# Breadboard.net
KiCad netlist of a schematic drawn in EAGLE
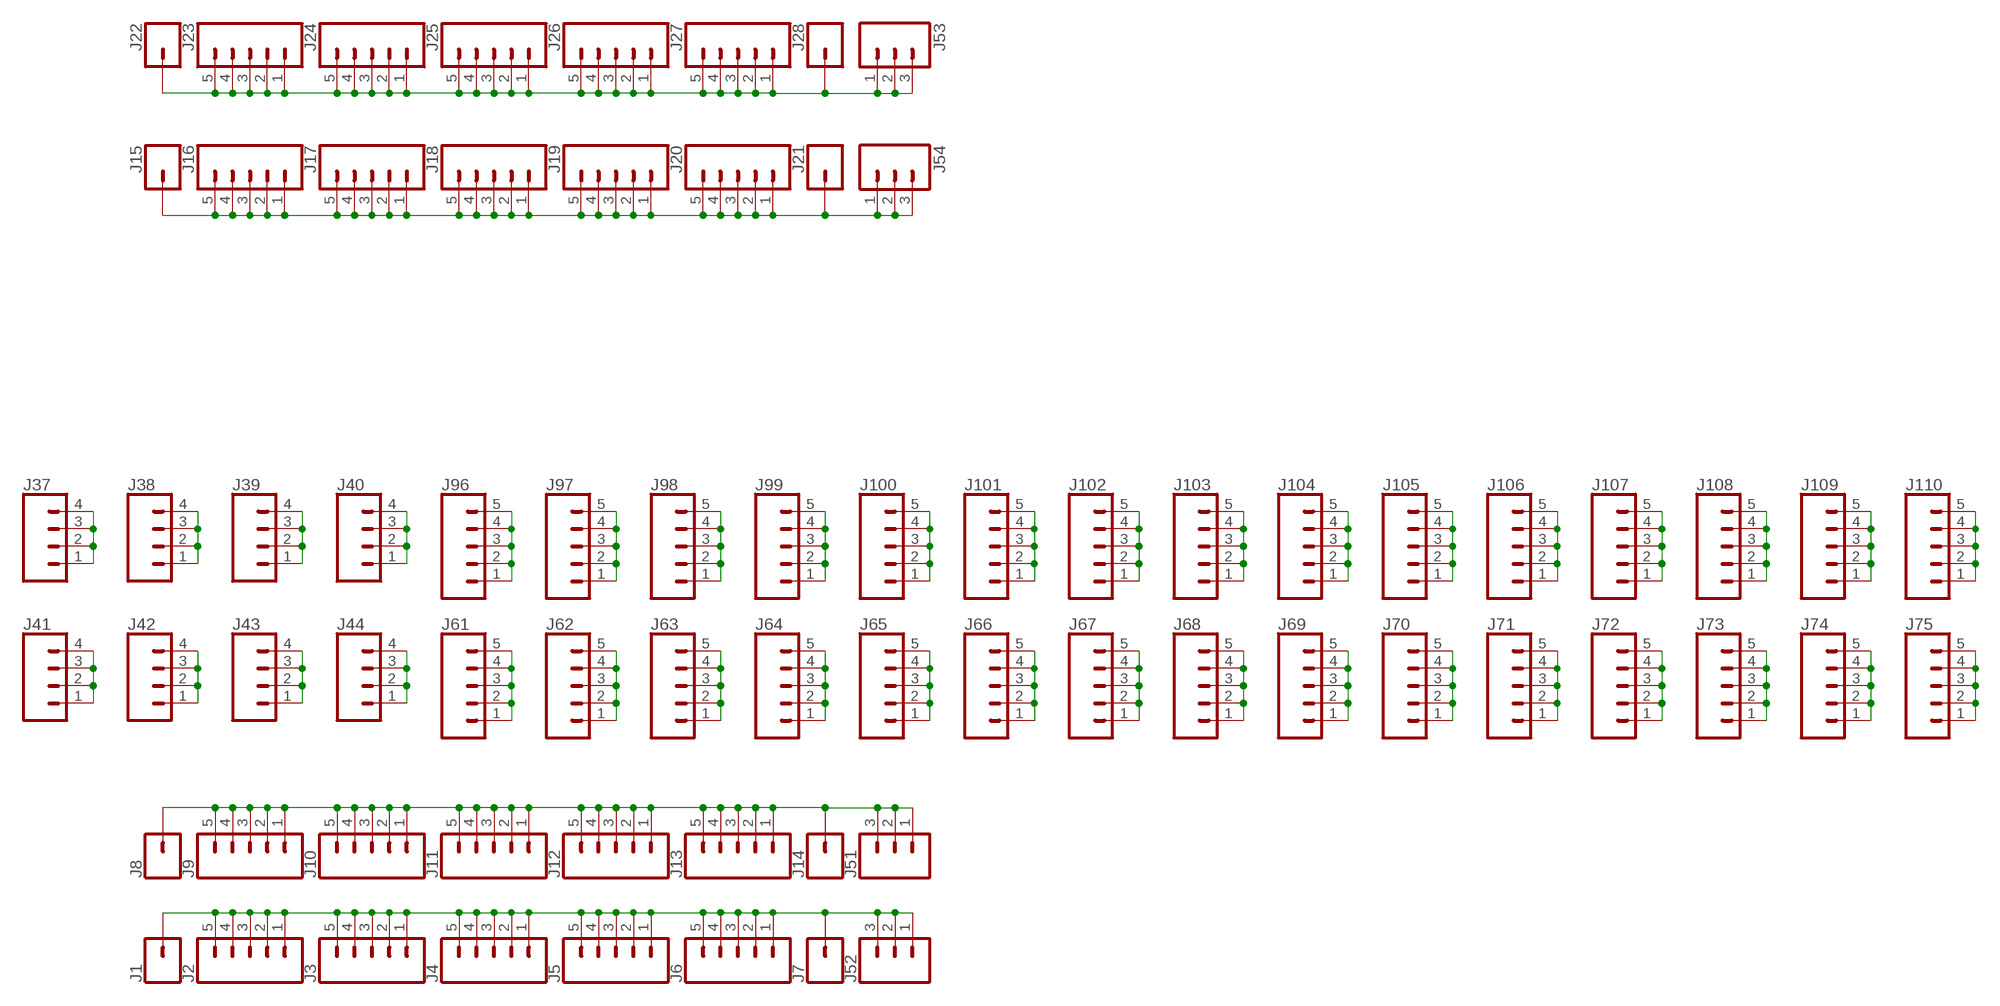
[diagram p0: schematic, sheet 1, part 1 of 2]
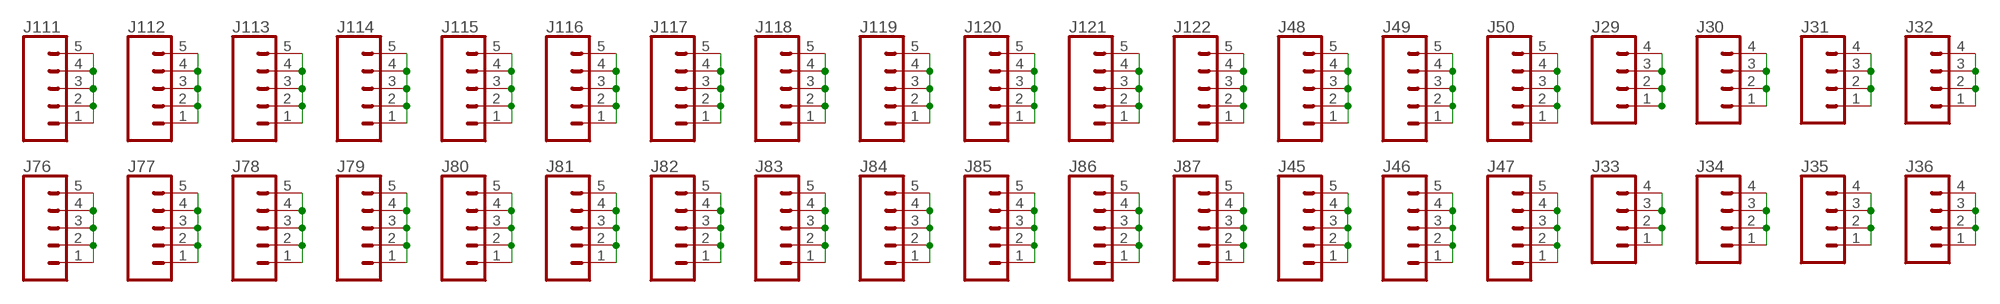
[diagram p1: schematic, sheet 1, part 2 of 2]
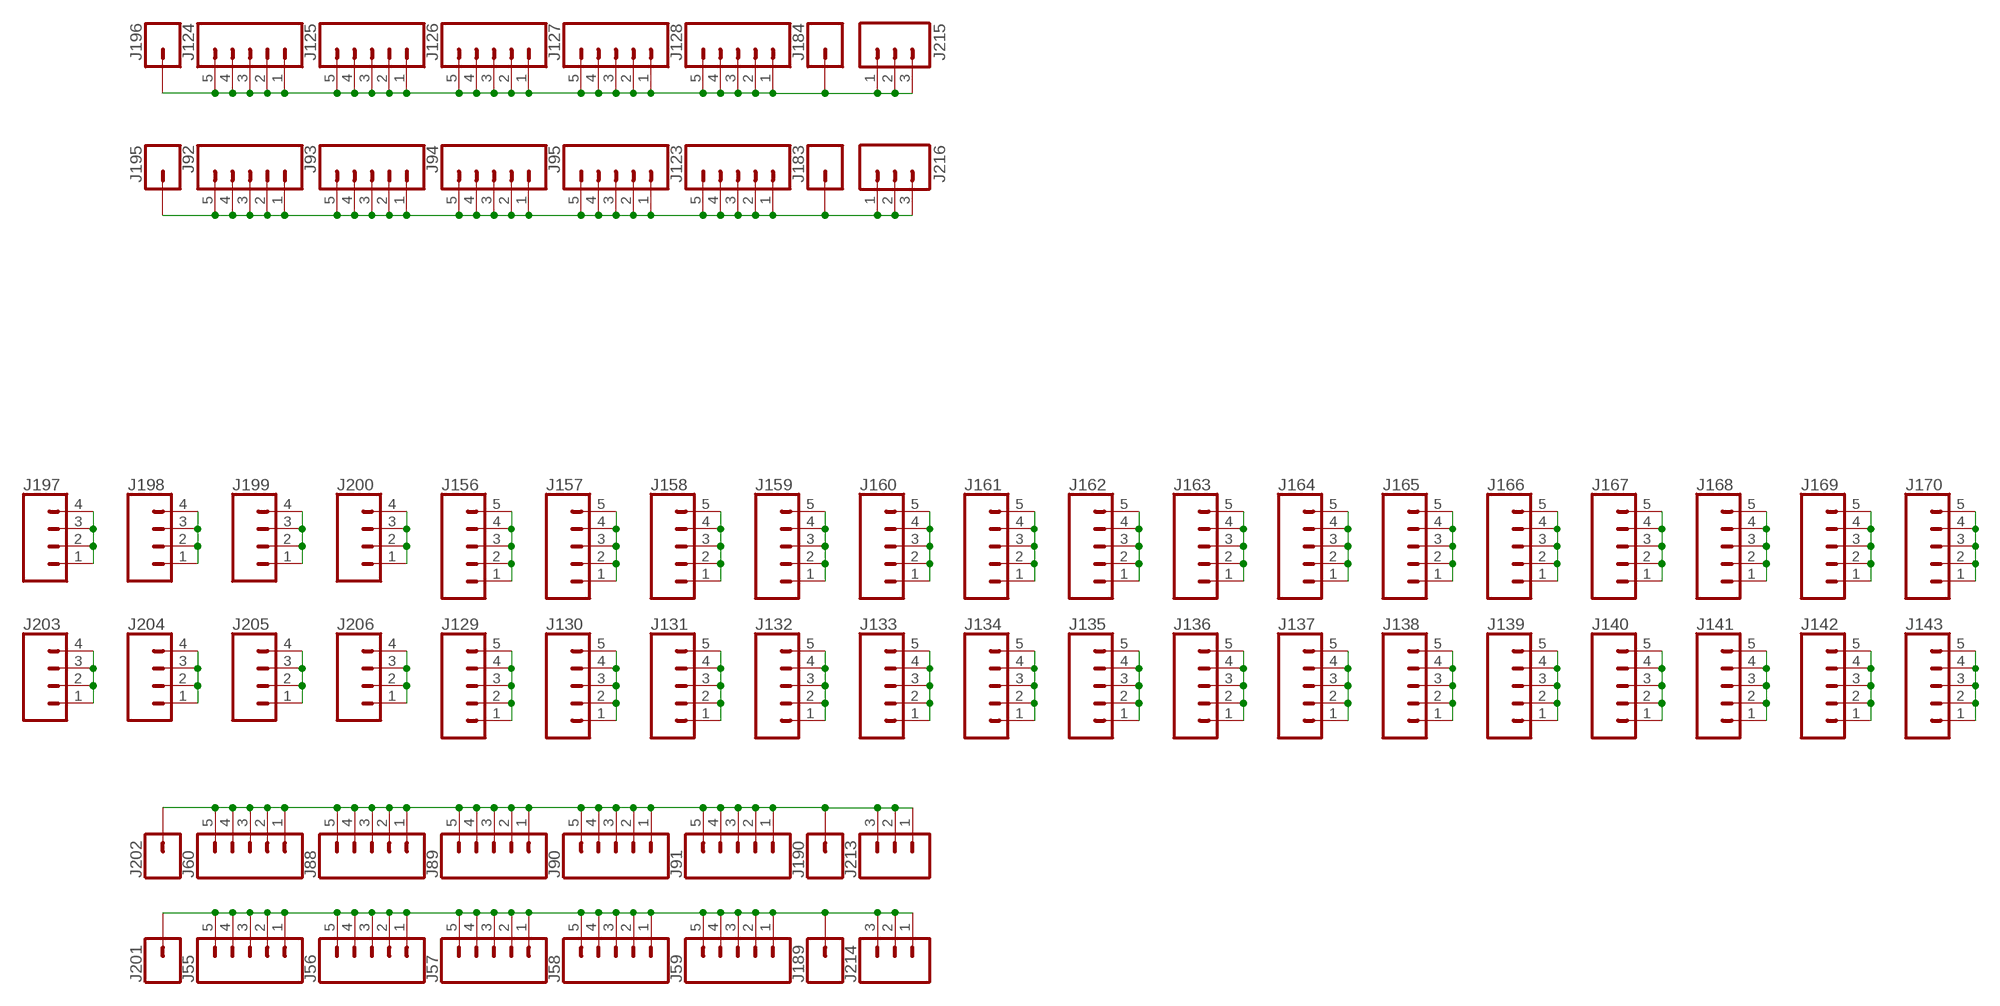
[diagram p2: schematic, sheet 2, part 1 of 2]
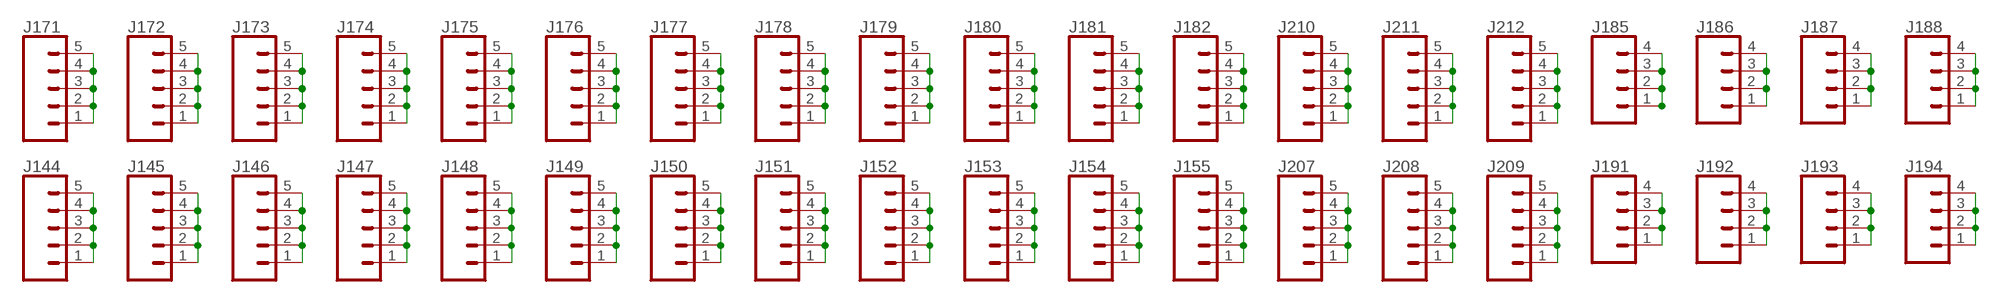
[diagram p3: schematic, sheet 2, part 2 of 2]

(export (version "E")
  (design (tool "Eeschema 10.0.6"))
  (components
    (comp (ref "J1")
      (value "CONN_01")
      (footprint "eagle-import:1X01")
      (libsource (lib "eagle-import") (part "CONN_01"))
    )
    (comp (ref "J2")
      (value "CONN_05")
      (footprint "eagle-import:1X05")
      (libsource (lib "eagle-import") (part "CONN_05"))
    )
    (comp (ref "J3")
      (value "CONN_05")
      (footprint "eagle-import:1X05")
      (libsource (lib "eagle-import") (part "CONN_05"))
    )
    (comp (ref "J4")
      (value "CONN_05")
      (footprint "eagle-import:1X05")
      (libsource (lib "eagle-import") (part "CONN_05"))
    )
    (comp (ref "J5")
      (value "CONN_05")
      (footprint "eagle-import:1X05")
      (libsource (lib "eagle-import") (part "CONN_05"))
    )
    (comp (ref "J6")
      (value "CONN_05")
      (footprint "eagle-import:1X05")
      (libsource (lib "eagle-import") (part "CONN_05"))
    )
    (comp (ref "J7")
      (value "CONN_01")
      (footprint "eagle-import:1X01")
      (libsource (lib "eagle-import") (part "CONN_01"))
    )
    (comp (ref "J8")
      (value "CONN_01")
      (footprint "eagle-import:1X01")
      (libsource (lib "eagle-import") (part "CONN_01"))
    )
    (comp (ref "J9")
      (value "CONN_05")
      (footprint "eagle-import:1X05")
      (libsource (lib "eagle-import") (part "CONN_05"))
    )
    (comp (ref "J10")
      (value "CONN_05")
      (footprint "eagle-import:1X05")
      (libsource (lib "eagle-import") (part "CONN_05"))
    )
    (comp (ref "J11")
      (value "CONN_05")
      (footprint "eagle-import:1X05")
      (libsource (lib "eagle-import") (part "CONN_05"))
    )
    (comp (ref "J12")
      (value "CONN_05")
      (footprint "eagle-import:1X05")
      (libsource (lib "eagle-import") (part "CONN_05"))
    )
    (comp (ref "J13")
      (value "CONN_05")
      (footprint "eagle-import:1X05")
      (libsource (lib "eagle-import") (part "CONN_05"))
    )
    (comp (ref "J14")
      (value "CONN_01")
      (footprint "eagle-import:1X01")
      (libsource (lib "eagle-import") (part "CONN_01"))
    )
    (comp (ref "J15")
      (value "CONN_01")
      (footprint "eagle-import:1X01")
      (libsource (lib "eagle-import") (part "CONN_01"))
    )
    (comp (ref "J16")
      (value "CONN_05")
      (footprint "eagle-import:1X05")
      (libsource (lib "eagle-import") (part "CONN_05"))
    )
    (comp (ref "J17")
      (value "CONN_05")
      (footprint "eagle-import:1X05")
      (libsource (lib "eagle-import") (part "CONN_05"))
    )
    (comp (ref "J18")
      (value "CONN_05")
      (footprint "eagle-import:1X05")
      (libsource (lib "eagle-import") (part "CONN_05"))
    )
    (comp (ref "J19")
      (value "CONN_05")
      (footprint "eagle-import:1X05")
      (libsource (lib "eagle-import") (part "CONN_05"))
    )
    (comp (ref "J20")
      (value "CONN_05")
      (footprint "eagle-import:1X05")
      (libsource (lib "eagle-import") (part "CONN_05"))
    )
    (comp (ref "J21")
      (value "CONN_01")
      (footprint "eagle-import:1X01")
      (libsource (lib "eagle-import") (part "CONN_01"))
    )
    (comp (ref "J22")
      (value "CONN_01")
      (footprint "eagle-import:1X01")
      (libsource (lib "eagle-import") (part "CONN_01"))
    )
    (comp (ref "J23")
      (value "CONN_05")
      (footprint "eagle-import:1X05")
      (libsource (lib "eagle-import") (part "CONN_05"))
    )
    (comp (ref "J24")
      (value "CONN_05")
      (footprint "eagle-import:1X05")
      (libsource (lib "eagle-import") (part "CONN_05"))
    )
    (comp (ref "J25")
      (value "CONN_05")
      (footprint "eagle-import:1X05")
      (libsource (lib "eagle-import") (part "CONN_05"))
    )
    (comp (ref "J26")
      (value "CONN_05")
      (footprint "eagle-import:1X05")
      (libsource (lib "eagle-import") (part "CONN_05"))
    )
    (comp (ref "J27")
      (value "CONN_05")
      (footprint "eagle-import:1X05")
      (libsource (lib "eagle-import") (part "CONN_05"))
    )
    (comp (ref "J28")
      (value "CONN_01")
      (footprint "eagle-import:1X01")
      (libsource (lib "eagle-import") (part "CONN_01"))
    )
    (comp (ref "J29")
      (value "CONN_04PTH")
      (footprint "eagle-import:1X04")
      (libsource (lib "eagle-import") (part "CONN_04PTH"))
    )
    (comp (ref "J30")
      (value "CONN_04PTH")
      (footprint "eagle-import:1X04")
      (libsource (lib "eagle-import") (part "CONN_04PTH"))
    )
    (comp (ref "J31")
      (value "CONN_04PTH")
      (footprint "eagle-import:1X04")
      (libsource (lib "eagle-import") (part "CONN_04PTH"))
    )
    (comp (ref "J32")
      (value "CONN_04PTH")
      (footprint "eagle-import:1X04")
      (libsource (lib "eagle-import") (part "CONN_04PTH"))
    )
    (comp (ref "J33")
      (value "CONN_04PTH")
      (footprint "eagle-import:1X04")
      (libsource (lib "eagle-import") (part "CONN_04PTH"))
    )
    (comp (ref "J34")
      (value "CONN_04PTH")
      (footprint "eagle-import:1X04")
      (libsource (lib "eagle-import") (part "CONN_04PTH"))
    )
    (comp (ref "J35")
      (value "CONN_04PTH")
      (footprint "eagle-import:1X04")
      (libsource (lib "eagle-import") (part "CONN_04PTH"))
    )
    (comp (ref "J36")
      (value "CONN_04PTH")
      (footprint "eagle-import:1X04")
      (libsource (lib "eagle-import") (part "CONN_04PTH"))
    )
    (comp (ref "J37")
      (value "CONN_04PTH")
      (footprint "eagle-import:1X04")
      (libsource (lib "eagle-import") (part "CONN_04PTH"))
    )
    (comp (ref "J38")
      (value "CONN_04PTH")
      (footprint "eagle-import:1X04")
      (libsource (lib "eagle-import") (part "CONN_04PTH"))
    )
    (comp (ref "J39")
      (value "CONN_04PTH")
      (footprint "eagle-import:1X04")
      (libsource (lib "eagle-import") (part "CONN_04PTH"))
    )
    (comp (ref "J40")
      (value "CONN_04PTH")
      (footprint "eagle-import:1X04")
      (libsource (lib "eagle-import") (part "CONN_04PTH"))
    )
    (comp (ref "J41")
      (value "CONN_04PTH")
      (footprint "eagle-import:1X04")
      (libsource (lib "eagle-import") (part "CONN_04PTH"))
    )
    (comp (ref "J42")
      (value "CONN_04PTH")
      (footprint "eagle-import:1X04")
      (libsource (lib "eagle-import") (part "CONN_04PTH"))
    )
    (comp (ref "J43")
      (value "CONN_04PTH")
      (footprint "eagle-import:1X04")
      (libsource (lib "eagle-import") (part "CONN_04PTH"))
    )
    (comp (ref "J44")
      (value "CONN_04PTH")
      (footprint "eagle-import:1X04")
      (libsource (lib "eagle-import") (part "CONN_04PTH"))
    )
    (comp (ref "J45")
      (value "CONN_05")
      (footprint "eagle-import:1X05")
      (libsource (lib "eagle-import") (part "CONN_05"))
    )
    (comp (ref "J46")
      (value "CONN_05")
      (footprint "eagle-import:1X05")
      (libsource (lib "eagle-import") (part "CONN_05"))
    )
    (comp (ref "J47")
      (value "CONN_05")
      (footprint "eagle-import:1X05")
      (libsource (lib "eagle-import") (part "CONN_05"))
    )
    (comp (ref "J48")
      (value "CONN_05")
      (footprint "eagle-import:1X05")
      (libsource (lib "eagle-import") (part "CONN_05"))
    )
    (comp (ref "J49")
      (value "CONN_05")
      (footprint "eagle-import:1X05")
      (libsource (lib "eagle-import") (part "CONN_05"))
    )
    (comp (ref "J50")
      (value "CONN_05")
      (footprint "eagle-import:1X05")
      (libsource (lib "eagle-import") (part "CONN_05"))
    )
    (comp (ref "J51")
      (value "455-1750-1-ND")
      (footprint "eagle-import:1X03")
      (libsource (lib "eagle-import") (part "CONN_03"))
    )
    (comp (ref "J52")
      (value "455-1750-1-ND")
      (footprint "eagle-import:1X03")
      (libsource (lib "eagle-import") (part "CONN_03"))
    )
    (comp (ref "J53")
      (value "455-1750-1-ND")
      (footprint "eagle-import:1X03")
      (libsource (lib "eagle-import") (part "CONN_03"))
    )
    (comp (ref "J54")
      (value "455-1750-1-ND")
      (footprint "eagle-import:1X03")
      (libsource (lib "eagle-import") (part "CONN_03"))
    )
    (comp (ref "J61")
      (value "CONN_05")
      (footprint "eagle-import:1X05")
      (libsource (lib "eagle-import") (part "CONN_05"))
    )
    (comp (ref "J62")
      (value "CONN_05")
      (footprint "eagle-import:1X05")
      (libsource (lib "eagle-import") (part "CONN_05"))
    )
    (comp (ref "J63")
      (value "CONN_05")
      (footprint "eagle-import:1X05")
      (libsource (lib "eagle-import") (part "CONN_05"))
    )
    (comp (ref "J64")
      (value "CONN_05")
      (footprint "eagle-import:1X05")
      (libsource (lib "eagle-import") (part "CONN_05"))
    )
    (comp (ref "J65")
      (value "CONN_05")
      (footprint "eagle-import:1X05")
      (libsource (lib "eagle-import") (part "CONN_05"))
    )
    (comp (ref "J66")
      (value "CONN_05")
      (footprint "eagle-import:1X05")
      (libsource (lib "eagle-import") (part "CONN_05"))
    )
    (comp (ref "J67")
      (value "CONN_05")
      (footprint "eagle-import:1X05")
      (libsource (lib "eagle-import") (part "CONN_05"))
    )
    (comp (ref "J68")
      (value "CONN_05")
      (footprint "eagle-import:1X05")
      (libsource (lib "eagle-import") (part "CONN_05"))
    )
    (comp (ref "J69")
      (value "CONN_05")
      (footprint "eagle-import:1X05")
      (libsource (lib "eagle-import") (part "CONN_05"))
    )
    (comp (ref "J70")
      (value "CONN_05")
      (footprint "eagle-import:1X05")
      (libsource (lib "eagle-import") (part "CONN_05"))
    )
    (comp (ref "J71")
      (value "CONN_05")
      (footprint "eagle-import:1X05")
      (libsource (lib "eagle-import") (part "CONN_05"))
    )
    (comp (ref "J72")
      (value "CONN_05")
      (footprint "eagle-import:1X05")
      (libsource (lib "eagle-import") (part "CONN_05"))
    )
    (comp (ref "J73")
      (value "CONN_05")
      (footprint "eagle-import:1X05")
      (libsource (lib "eagle-import") (part "CONN_05"))
    )
    (comp (ref "J74")
      (value "CONN_05")
      (footprint "eagle-import:1X05")
      (libsource (lib "eagle-import") (part "CONN_05"))
    )
    (comp (ref "J75")
      (value "CONN_05")
      (footprint "eagle-import:1X05")
      (libsource (lib "eagle-import") (part "CONN_05"))
    )
    (comp (ref "J76")
      (value "CONN_05")
      (footprint "eagle-import:1X05")
      (libsource (lib "eagle-import") (part "CONN_05"))
    )
    (comp (ref "J77")
      (value "CONN_05")
      (footprint "eagle-import:1X05")
      (libsource (lib "eagle-import") (part "CONN_05"))
    )
    (comp (ref "J78")
      (value "CONN_05")
      (footprint "eagle-import:1X05")
      (libsource (lib "eagle-import") (part "CONN_05"))
    )
    (comp (ref "J79")
      (value "CONN_05")
      (footprint "eagle-import:1X05")
      (libsource (lib "eagle-import") (part "CONN_05"))
    )
    (comp (ref "J80")
      (value "CONN_05")
      (footprint "eagle-import:1X05")
      (libsource (lib "eagle-import") (part "CONN_05"))
    )
    (comp (ref "J81")
      (value "CONN_05")
      (footprint "eagle-import:1X05")
      (libsource (lib "eagle-import") (part "CONN_05"))
    )
    (comp (ref "J82")
      (value "CONN_05")
      (footprint "eagle-import:1X05")
      (libsource (lib "eagle-import") (part "CONN_05"))
    )
    (comp (ref "J83")
      (value "CONN_05")
      (footprint "eagle-import:1X05")
      (libsource (lib "eagle-import") (part "CONN_05"))
    )
    (comp (ref "J84")
      (value "CONN_05")
      (footprint "eagle-import:1X05")
      (libsource (lib "eagle-import") (part "CONN_05"))
    )
    (comp (ref "J85")
      (value "CONN_05")
      (footprint "eagle-import:1X05")
      (libsource (lib "eagle-import") (part "CONN_05"))
    )
    (comp (ref "J86")
      (value "CONN_05")
      (footprint "eagle-import:1X05")
      (libsource (lib "eagle-import") (part "CONN_05"))
    )
    (comp (ref "J87")
      (value "CONN_05")
      (footprint "eagle-import:1X05")
      (libsource (lib "eagle-import") (part "CONN_05"))
    )
    (comp (ref "J96")
      (value "CONN_05")
      (footprint "eagle-import:1X05")
      (libsource (lib "eagle-import") (part "CONN_05"))
    )
    (comp (ref "J97")
      (value "CONN_05")
      (footprint "eagle-import:1X05")
      (libsource (lib "eagle-import") (part "CONN_05"))
    )
    (comp (ref "J98")
      (value "CONN_05")
      (footprint "eagle-import:1X05")
      (libsource (lib "eagle-import") (part "CONN_05"))
    )
    (comp (ref "J99")
      (value "CONN_05")
      (footprint "eagle-import:1X05")
      (libsource (lib "eagle-import") (part "CONN_05"))
    )
    (comp (ref "J100")
      (value "CONN_05")
      (footprint "eagle-import:1X05")
      (libsource (lib "eagle-import") (part "CONN_05"))
    )
    (comp (ref "J101")
      (value "CONN_05")
      (footprint "eagle-import:1X05")
      (libsource (lib "eagle-import") (part "CONN_05"))
    )
    (comp (ref "J102")
      (value "CONN_05")
      (footprint "eagle-import:1X05")
      (libsource (lib "eagle-import") (part "CONN_05"))
    )
    (comp (ref "J103")
      (value "CONN_05")
      (footprint "eagle-import:1X05")
      (libsource (lib "eagle-import") (part "CONN_05"))
    )
    (comp (ref "J104")
      (value "CONN_05")
      (footprint "eagle-import:1X05")
      (libsource (lib "eagle-import") (part "CONN_05"))
    )
    (comp (ref "J105")
      (value "CONN_05")
      (footprint "eagle-import:1X05")
      (libsource (lib "eagle-import") (part "CONN_05"))
    )
    (comp (ref "J106")
      (value "CONN_05")
      (footprint "eagle-import:1X05")
      (libsource (lib "eagle-import") (part "CONN_05"))
    )
    (comp (ref "J107")
      (value "CONN_05")
      (footprint "eagle-import:1X05")
      (libsource (lib "eagle-import") (part "CONN_05"))
    )
    (comp (ref "J108")
      (value "CONN_05")
      (footprint "eagle-import:1X05")
      (libsource (lib "eagle-import") (part "CONN_05"))
    )
    (comp (ref "J109")
      (value "CONN_05")
      (footprint "eagle-import:1X05")
      (libsource (lib "eagle-import") (part "CONN_05"))
    )
    (comp (ref "J110")
      (value "CONN_05")
      (footprint "eagle-import:1X05")
      (libsource (lib "eagle-import") (part "CONN_05"))
    )
    (comp (ref "J111")
      (value "CONN_05")
      (footprint "eagle-import:1X05")
      (libsource (lib "eagle-import") (part "CONN_05"))
    )
    (comp (ref "J112")
      (value "CONN_05")
      (footprint "eagle-import:1X05")
      (libsource (lib "eagle-import") (part "CONN_05"))
    )
    (comp (ref "J113")
      (value "CONN_05")
      (footprint "eagle-import:1X05")
      (libsource (lib "eagle-import") (part "CONN_05"))
    )
    (comp (ref "J114")
      (value "CONN_05")
      (footprint "eagle-import:1X05")
      (libsource (lib "eagle-import") (part "CONN_05"))
    )
    (comp (ref "J115")
      (value "CONN_05")
      (footprint "eagle-import:1X05")
      (libsource (lib "eagle-import") (part "CONN_05"))
    )
    (comp (ref "J116")
      (value "CONN_05")
      (footprint "eagle-import:1X05")
      (libsource (lib "eagle-import") (part "CONN_05"))
    )
    (comp (ref "J117")
      (value "CONN_05")
      (footprint "eagle-import:1X05")
      (libsource (lib "eagle-import") (part "CONN_05"))
    )
    (comp (ref "J118")
      (value "CONN_05")
      (footprint "eagle-import:1X05")
      (libsource (lib "eagle-import") (part "CONN_05"))
    )
    (comp (ref "J119")
      (value "CONN_05")
      (footprint "eagle-import:1X05")
      (libsource (lib "eagle-import") (part "CONN_05"))
    )
    (comp (ref "J120")
      (value "CONN_05")
      (footprint "eagle-import:1X05")
      (libsource (lib "eagle-import") (part "CONN_05"))
    )
    (comp (ref "J121")
      (value "CONN_05")
      (footprint "eagle-import:1X05")
      (libsource (lib "eagle-import") (part "CONN_05"))
    )
    (comp (ref "J122")
      (value "CONN_05")
      (footprint "eagle-import:1X05")
      (libsource (lib "eagle-import") (part "CONN_05"))
    )
    (comp (ref "J55")
      (value "CONN_05")
      (footprint "eagle-import:1X05")
      (libsource (lib "eagle-import") (part "CONN_05"))
    )
    (comp (ref "J56")
      (value "CONN_05")
      (footprint "eagle-import:1X05")
      (libsource (lib "eagle-import") (part "CONN_05"))
    )
    (comp (ref "J57")
      (value "CONN_05")
      (footprint "eagle-import:1X05")
      (libsource (lib "eagle-import") (part "CONN_05"))
    )
    (comp (ref "J58")
      (value "CONN_05")
      (footprint "eagle-import:1X05")
      (libsource (lib "eagle-import") (part "CONN_05"))
    )
    (comp (ref "J59")
      (value "CONN_05")
      (footprint "eagle-import:1X05")
      (libsource (lib "eagle-import") (part "CONN_05"))
    )
    (comp (ref "J60")
      (value "CONN_05")
      (footprint "eagle-import:1X05")
      (libsource (lib "eagle-import") (part "CONN_05"))
    )
    (comp (ref "J88")
      (value "CONN_05")
      (footprint "eagle-import:1X05")
      (libsource (lib "eagle-import") (part "CONN_05"))
    )
    (comp (ref "J89")
      (value "CONN_05")
      (footprint "eagle-import:1X05")
      (libsource (lib "eagle-import") (part "CONN_05"))
    )
    (comp (ref "J90")
      (value "CONN_05")
      (footprint "eagle-import:1X05")
      (libsource (lib "eagle-import") (part "CONN_05"))
    )
    (comp (ref "J91")
      (value "CONN_05")
      (footprint "eagle-import:1X05")
      (libsource (lib "eagle-import") (part "CONN_05"))
    )
    (comp (ref "J92")
      (value "CONN_05")
      (footprint "eagle-import:1X05")
      (libsource (lib "eagle-import") (part "CONN_05"))
    )
    (comp (ref "J93")
      (value "CONN_05")
      (footprint "eagle-import:1X05")
      (libsource (lib "eagle-import") (part "CONN_05"))
    )
    (comp (ref "J94")
      (value "CONN_05")
      (footprint "eagle-import:1X05")
      (libsource (lib "eagle-import") (part "CONN_05"))
    )
    (comp (ref "J95")
      (value "CONN_05")
      (footprint "eagle-import:1X05")
      (libsource (lib "eagle-import") (part "CONN_05"))
    )
    (comp (ref "J123")
      (value "CONN_05")
      (footprint "eagle-import:1X05")
      (libsource (lib "eagle-import") (part "CONN_05"))
    )
    (comp (ref "J124")
      (value "CONN_05")
      (footprint "eagle-import:1X05")
      (libsource (lib "eagle-import") (part "CONN_05"))
    )
    (comp (ref "J125")
      (value "CONN_05")
      (footprint "eagle-import:1X05")
      (libsource (lib "eagle-import") (part "CONN_05"))
    )
    (comp (ref "J126")
      (value "CONN_05")
      (footprint "eagle-import:1X05")
      (libsource (lib "eagle-import") (part "CONN_05"))
    )
    (comp (ref "J127")
      (value "CONN_05")
      (footprint "eagle-import:1X05")
      (libsource (lib "eagle-import") (part "CONN_05"))
    )
    (comp (ref "J128")
      (value "CONN_05")
      (footprint "eagle-import:1X05")
      (libsource (lib "eagle-import") (part "CONN_05"))
    )
    (comp (ref "J129")
      (value "CONN_05")
      (footprint "eagle-import:1X05")
      (libsource (lib "eagle-import") (part "CONN_05"))
    )
    (comp (ref "J130")
      (value "CONN_05")
      (footprint "eagle-import:1X05")
      (libsource (lib "eagle-import") (part "CONN_05"))
    )
    (comp (ref "J131")
      (value "CONN_05")
      (footprint "eagle-import:1X05")
      (libsource (lib "eagle-import") (part "CONN_05"))
    )
    (comp (ref "J132")
      (value "CONN_05")
      (footprint "eagle-import:1X05")
      (libsource (lib "eagle-import") (part "CONN_05"))
    )
    (comp (ref "J133")
      (value "CONN_05")
      (footprint "eagle-import:1X05")
      (libsource (lib "eagle-import") (part "CONN_05"))
    )
    (comp (ref "J134")
      (value "CONN_05")
      (footprint "eagle-import:1X05")
      (libsource (lib "eagle-import") (part "CONN_05"))
    )
    (comp (ref "J135")
      (value "CONN_05")
      (footprint "eagle-import:1X05")
      (libsource (lib "eagle-import") (part "CONN_05"))
    )
    (comp (ref "J136")
      (value "CONN_05")
      (footprint "eagle-import:1X05")
      (libsource (lib "eagle-import") (part "CONN_05"))
    )
    (comp (ref "J137")
      (value "CONN_05")
      (footprint "eagle-import:1X05")
      (libsource (lib "eagle-import") (part "CONN_05"))
    )
    (comp (ref "J138")
      (value "CONN_05")
      (footprint "eagle-import:1X05")
      (libsource (lib "eagle-import") (part "CONN_05"))
    )
    (comp (ref "J139")
      (value "CONN_05")
      (footprint "eagle-import:1X05")
      (libsource (lib "eagle-import") (part "CONN_05"))
    )
    (comp (ref "J140")
      (value "CONN_05")
      (footprint "eagle-import:1X05")
      (libsource (lib "eagle-import") (part "CONN_05"))
    )
    (comp (ref "J141")
      (value "CONN_05")
      (footprint "eagle-import:1X05")
      (libsource (lib "eagle-import") (part "CONN_05"))
    )
    (comp (ref "J142")
      (value "CONN_05")
      (footprint "eagle-import:1X05")
      (libsource (lib "eagle-import") (part "CONN_05"))
    )
    (comp (ref "J143")
      (value "CONN_05")
      (footprint "eagle-import:1X05")
      (libsource (lib "eagle-import") (part "CONN_05"))
    )
    (comp (ref "J144")
      (value "CONN_05")
      (footprint "eagle-import:1X05")
      (libsource (lib "eagle-import") (part "CONN_05"))
    )
    (comp (ref "J145")
      (value "CONN_05")
      (footprint "eagle-import:1X05")
      (libsource (lib "eagle-import") (part "CONN_05"))
    )
    (comp (ref "J146")
      (value "CONN_05")
      (footprint "eagle-import:1X05")
      (libsource (lib "eagle-import") (part "CONN_05"))
    )
    (comp (ref "J147")
      (value "CONN_05")
      (footprint "eagle-import:1X05")
      (libsource (lib "eagle-import") (part "CONN_05"))
    )
    (comp (ref "J148")
      (value "CONN_05")
      (footprint "eagle-import:1X05")
      (libsource (lib "eagle-import") (part "CONN_05"))
    )
    (comp (ref "J149")
      (value "CONN_05")
      (footprint "eagle-import:1X05")
      (libsource (lib "eagle-import") (part "CONN_05"))
    )
    (comp (ref "J150")
      (value "CONN_05")
      (footprint "eagle-import:1X05")
      (libsource (lib "eagle-import") (part "CONN_05"))
    )
    (comp (ref "J151")
      (value "CONN_05")
      (footprint "eagle-import:1X05")
      (libsource (lib "eagle-import") (part "CONN_05"))
    )
    (comp (ref "J152")
      (value "CONN_05")
      (footprint "eagle-import:1X05")
      (libsource (lib "eagle-import") (part "CONN_05"))
    )
    (comp (ref "J153")
      (value "CONN_05")
      (footprint "eagle-import:1X05")
      (libsource (lib "eagle-import") (part "CONN_05"))
    )
    (comp (ref "J154")
      (value "CONN_05")
      (footprint "eagle-import:1X05")
      (libsource (lib "eagle-import") (part "CONN_05"))
    )
    (comp (ref "J155")
      (value "CONN_05")
      (footprint "eagle-import:1X05")
      (libsource (lib "eagle-import") (part "CONN_05"))
    )
    (comp (ref "J156")
      (value "CONN_05")
      (footprint "eagle-import:1X05")
      (libsource (lib "eagle-import") (part "CONN_05"))
    )
    (comp (ref "J157")
      (value "CONN_05")
      (footprint "eagle-import:1X05")
      (libsource (lib "eagle-import") (part "CONN_05"))
    )
    (comp (ref "J158")
      (value "CONN_05")
      (footprint "eagle-import:1X05")
      (libsource (lib "eagle-import") (part "CONN_05"))
    )
    (comp (ref "J159")
      (value "CONN_05")
      (footprint "eagle-import:1X05")
      (libsource (lib "eagle-import") (part "CONN_05"))
    )
    (comp (ref "J160")
      (value "CONN_05")
      (footprint "eagle-import:1X05")
      (libsource (lib "eagle-import") (part "CONN_05"))
    )
    (comp (ref "J161")
      (value "CONN_05")
      (footprint "eagle-import:1X05")
      (libsource (lib "eagle-import") (part "CONN_05"))
    )
    (comp (ref "J162")
      (value "CONN_05")
      (footprint "eagle-import:1X05")
      (libsource (lib "eagle-import") (part "CONN_05"))
    )
    (comp (ref "J163")
      (value "CONN_05")
      (footprint "eagle-import:1X05")
      (libsource (lib "eagle-import") (part "CONN_05"))
    )
    (comp (ref "J164")
      (value "CONN_05")
      (footprint "eagle-import:1X05")
      (libsource (lib "eagle-import") (part "CONN_05"))
    )
    (comp (ref "J165")
      (value "CONN_05")
      (footprint "eagle-import:1X05")
      (libsource (lib "eagle-import") (part "CONN_05"))
    )
    (comp (ref "J166")
      (value "CONN_05")
      (footprint "eagle-import:1X05")
      (libsource (lib "eagle-import") (part "CONN_05"))
    )
    (comp (ref "J167")
      (value "CONN_05")
      (footprint "eagle-import:1X05")
      (libsource (lib "eagle-import") (part "CONN_05"))
    )
    (comp (ref "J168")
      (value "CONN_05")
      (footprint "eagle-import:1X05")
      (libsource (lib "eagle-import") (part "CONN_05"))
    )
    (comp (ref "J169")
      (value "CONN_05")
      (footprint "eagle-import:1X05")
      (libsource (lib "eagle-import") (part "CONN_05"))
    )
    (comp (ref "J170")
      (value "CONN_05")
      (footprint "eagle-import:1X05")
      (libsource (lib "eagle-import") (part "CONN_05"))
    )
    (comp (ref "J171")
      (value "CONN_05")
      (footprint "eagle-import:1X05")
      (libsource (lib "eagle-import") (part "CONN_05"))
    )
    (comp (ref "J172")
      (value "CONN_05")
      (footprint "eagle-import:1X05")
      (libsource (lib "eagle-import") (part "CONN_05"))
    )
    (comp (ref "J173")
      (value "CONN_05")
      (footprint "eagle-import:1X05")
      (libsource (lib "eagle-import") (part "CONN_05"))
    )
    (comp (ref "J174")
      (value "CONN_05")
      (footprint "eagle-import:1X05")
      (libsource (lib "eagle-import") (part "CONN_05"))
    )
    (comp (ref "J175")
      (value "CONN_05")
      (footprint "eagle-import:1X05")
      (libsource (lib "eagle-import") (part "CONN_05"))
    )
    (comp (ref "J176")
      (value "CONN_05")
      (footprint "eagle-import:1X05")
      (libsource (lib "eagle-import") (part "CONN_05"))
    )
    (comp (ref "J177")
      (value "CONN_05")
      (footprint "eagle-import:1X05")
      (libsource (lib "eagle-import") (part "CONN_05"))
    )
    (comp (ref "J178")
      (value "CONN_05")
      (footprint "eagle-import:1X05")
      (libsource (lib "eagle-import") (part "CONN_05"))
    )
    (comp (ref "J179")
      (value "CONN_05")
      (footprint "eagle-import:1X05")
      (libsource (lib "eagle-import") (part "CONN_05"))
    )
    (comp (ref "J180")
      (value "CONN_05")
      (footprint "eagle-import:1X05")
      (libsource (lib "eagle-import") (part "CONN_05"))
    )
    (comp (ref "J181")
      (value "CONN_05")
      (footprint "eagle-import:1X05")
      (libsource (lib "eagle-import") (part "CONN_05"))
    )
    (comp (ref "J182")
      (value "CONN_05")
      (footprint "eagle-import:1X05")
      (libsource (lib "eagle-import") (part "CONN_05"))
    )
    (comp (ref "J183")
      (value "CONN_01")
      (footprint "eagle-import:1X01")
      (libsource (lib "eagle-import") (part "CONN_01"))
    )
    (comp (ref "J184")
      (value "CONN_01")
      (footprint "eagle-import:1X01")
      (libsource (lib "eagle-import") (part "CONN_01"))
    )
    (comp (ref "J185")
      (value "CONN_04PTH")
      (footprint "eagle-import:1X04")
      (libsource (lib "eagle-import") (part "CONN_04PTH"))
    )
    (comp (ref "J186")
      (value "CONN_04PTH")
      (footprint "eagle-import:1X04")
      (libsource (lib "eagle-import") (part "CONN_04PTH"))
    )
    (comp (ref "J187")
      (value "CONN_04PTH")
      (footprint "eagle-import:1X04")
      (libsource (lib "eagle-import") (part "CONN_04PTH"))
    )
    (comp (ref "J188")
      (value "CONN_04PTH")
      (footprint "eagle-import:1X04")
      (libsource (lib "eagle-import") (part "CONN_04PTH"))
    )
    (comp (ref "J189")
      (value "CONN_01")
      (footprint "eagle-import:1X01")
      (libsource (lib "eagle-import") (part "CONN_01"))
    )
    (comp (ref "J190")
      (value "CONN_01")
      (footprint "eagle-import:1X01")
      (libsource (lib "eagle-import") (part "CONN_01"))
    )
    (comp (ref "J191")
      (value "CONN_04PTH")
      (footprint "eagle-import:1X04")
      (libsource (lib "eagle-import") (part "CONN_04PTH"))
    )
    (comp (ref "J192")
      (value "CONN_04PTH")
      (footprint "eagle-import:1X04")
      (libsource (lib "eagle-import") (part "CONN_04PTH"))
    )
    (comp (ref "J193")
      (value "CONN_04PTH")
      (footprint "eagle-import:1X04")
      (libsource (lib "eagle-import") (part "CONN_04PTH"))
    )
    (comp (ref "J194")
      (value "CONN_04PTH")
      (footprint "eagle-import:1X04")
      (libsource (lib "eagle-import") (part "CONN_04PTH"))
    )
    (comp (ref "J195")
      (value "CONN_01")
      (footprint "eagle-import:1X01")
      (libsource (lib "eagle-import") (part "CONN_01"))
    )
    (comp (ref "J196")
      (value "CONN_01")
      (footprint "eagle-import:1X01")
      (libsource (lib "eagle-import") (part "CONN_01"))
    )
    (comp (ref "J197")
      (value "CONN_04PTH")
      (footprint "eagle-import:1X04")
      (libsource (lib "eagle-import") (part "CONN_04PTH"))
    )
    (comp (ref "J198")
      (value "CONN_04PTH")
      (footprint "eagle-import:1X04")
      (libsource (lib "eagle-import") (part "CONN_04PTH"))
    )
    (comp (ref "J199")
      (value "CONN_04PTH")
      (footprint "eagle-import:1X04")
      (libsource (lib "eagle-import") (part "CONN_04PTH"))
    )
    (comp (ref "J200")
      (value "CONN_04PTH")
      (footprint "eagle-import:1X04")
      (libsource (lib "eagle-import") (part "CONN_04PTH"))
    )
    (comp (ref "J201")
      (value "CONN_01")
      (footprint "eagle-import:1X01")
      (libsource (lib "eagle-import") (part "CONN_01"))
    )
    (comp (ref "J202")
      (value "CONN_01")
      (footprint "eagle-import:1X01")
      (libsource (lib "eagle-import") (part "CONN_01"))
    )
    (comp (ref "J203")
      (value "CONN_04PTH")
      (footprint "eagle-import:1X04")
      (libsource (lib "eagle-import") (part "CONN_04PTH"))
    )
    (comp (ref "J204")
      (value "CONN_04PTH")
      (footprint "eagle-import:1X04")
      (libsource (lib "eagle-import") (part "CONN_04PTH"))
    )
    (comp (ref "J205")
      (value "CONN_04PTH")
      (footprint "eagle-import:1X04")
      (libsource (lib "eagle-import") (part "CONN_04PTH"))
    )
    (comp (ref "J206")
      (value "CONN_04PTH")
      (footprint "eagle-import:1X04")
      (libsource (lib "eagle-import") (part "CONN_04PTH"))
    )
    (comp (ref "J207")
      (value "CONN_05")
      (footprint "eagle-import:1X05")
      (libsource (lib "eagle-import") (part "CONN_05"))
    )
    (comp (ref "J208")
      (value "CONN_05")
      (footprint "eagle-import:1X05")
      (libsource (lib "eagle-import") (part "CONN_05"))
    )
    (comp (ref "J209")
      (value "CONN_05")
      (footprint "eagle-import:1X05")
      (libsource (lib "eagle-import") (part "CONN_05"))
    )
    (comp (ref "J210")
      (value "CONN_05")
      (footprint "eagle-import:1X05")
      (libsource (lib "eagle-import") (part "CONN_05"))
    )
    (comp (ref "J211")
      (value "CONN_05")
      (footprint "eagle-import:1X05")
      (libsource (lib "eagle-import") (part "CONN_05"))
    )
    (comp (ref "J212")
      (value "CONN_05")
      (footprint "eagle-import:1X05")
      (libsource (lib "eagle-import") (part "CONN_05"))
    )
    (comp (ref "J213")
      (value "455-1750-1-ND")
      (footprint "eagle-import:1X03")
      (libsource (lib "eagle-import") (part "CONN_03"))
    )
    (comp (ref "J214")
      (value "455-1750-1-ND")
      (footprint "eagle-import:1X03")
      (libsource (lib "eagle-import") (part "CONN_03"))
    )
    (comp (ref "J215")
      (value "455-1750-1-ND")
      (footprint "eagle-import:1X03")
      (libsource (lib "eagle-import") (part "CONN_03"))
    )
    (comp (ref "J216")
      (value "455-1750-1-ND")
      (footprint "eagle-import:1X03")
      (libsource (lib "eagle-import") (part "CONN_03"))
    )
  )
  (nets
    (net (code "1") (name "Net-(J1-Pad1)") (class "Default")
      (node (ref "J1") (pin "1") (pinfunction "1_1") (pintype "passive"))
      (node (ref "J2") (pin "1") (pinfunction "1_1") (pintype "passive"))
      (node (ref "J2") (pin "2") (pinfunction "2_2") (pintype "passive"))
      (node (ref "J2") (pin "3") (pinfunction "3_3") (pintype "passive"))
      (node (ref "J2") (pin "4") (pinfunction "4_4") (pintype "passive"))
      (node (ref "J2") (pin "5") (pinfunction "5_5") (pintype "passive"))
      (node (ref "J3") (pin "1") (pinfunction "1_1") (pintype "passive"))
      (node (ref "J3") (pin "2") (pinfunction "2_2") (pintype "passive"))
      (node (ref "J3") (pin "3") (pinfunction "3_3") (pintype "passive"))
      (node (ref "J3") (pin "4") (pinfunction "4_4") (pintype "passive"))
      (node (ref "J3") (pin "5") (pinfunction "5_5") (pintype "passive"))
      (node (ref "J4") (pin "1") (pinfunction "1_1") (pintype "passive"))
      (node (ref "J4") (pin "2") (pinfunction "2_2") (pintype "passive"))
      (node (ref "J4") (pin "3") (pinfunction "3_3") (pintype "passive"))
      (node (ref "J4") (pin "4") (pinfunction "4_4") (pintype "passive"))
      (node (ref "J4") (pin "5") (pinfunction "5_5") (pintype "passive"))
      (node (ref "J5") (pin "1") (pinfunction "1_1") (pintype "passive"))
      (node (ref "J5") (pin "2") (pinfunction "2_2") (pintype "passive"))
      (node (ref "J5") (pin "3") (pinfunction "3_3") (pintype "passive"))
      (node (ref "J5") (pin "4") (pinfunction "4_4") (pintype "passive"))
      (node (ref "J5") (pin "5") (pinfunction "5_5") (pintype "passive"))
      (node (ref "J52") (pin "1") (pinfunction "1_1") (pintype "passive"))
      (node (ref "J52") (pin "2") (pinfunction "2_2") (pintype "passive"))
      (node (ref "J52") (pin "3") (pinfunction "3_3") (pintype "passive"))
      (node (ref "J6") (pin "1") (pinfunction "1_1") (pintype "passive"))
      (node (ref "J6") (pin "2") (pinfunction "2_2") (pintype "passive"))
      (node (ref "J6") (pin "3") (pinfunction "3_3") (pintype "passive"))
      (node (ref "J6") (pin "4") (pinfunction "4_4") (pintype "passive"))
      (node (ref "J6") (pin "5") (pinfunction "5_5") (pintype "passive"))
      (node (ref "J7") (pin "1") (pinfunction "1_1") (pintype "passive"))
    )
    (net (code "2") (name "Net-(J10-Pad1)") (class "Default")
      (node (ref "J10") (pin "1") (pinfunction "1_1") (pintype "passive"))
      (node (ref "J10") (pin "2") (pinfunction "2_2") (pintype "passive"))
      (node (ref "J10") (pin "3") (pinfunction "3_3") (pintype "passive"))
      (node (ref "J10") (pin "4") (pinfunction "4_4") (pintype "passive"))
      (node (ref "J10") (pin "5") (pinfunction "5_5") (pintype "passive"))
      (node (ref "J11") (pin "1") (pinfunction "1_1") (pintype "passive"))
      (node (ref "J11") (pin "2") (pinfunction "2_2") (pintype "passive"))
      (node (ref "J11") (pin "3") (pinfunction "3_3") (pintype "passive"))
      (node (ref "J11") (pin "4") (pinfunction "4_4") (pintype "passive"))
      (node (ref "J11") (pin "5") (pinfunction "5_5") (pintype "passive"))
      (node (ref "J12") (pin "1") (pinfunction "1_1") (pintype "passive"))
      (node (ref "J12") (pin "2") (pinfunction "2_2") (pintype "passive"))
      (node (ref "J12") (pin "3") (pinfunction "3_3") (pintype "passive"))
      (node (ref "J12") (pin "4") (pinfunction "4_4") (pintype "passive"))
      (node (ref "J12") (pin "5") (pinfunction "5_5") (pintype "passive"))
      (node (ref "J13") (pin "1") (pinfunction "1_1") (pintype "passive"))
      (node (ref "J13") (pin "2") (pinfunction "2_2") (pintype "passive"))
      (node (ref "J13") (pin "3") (pinfunction "3_3") (pintype "passive"))
      (node (ref "J13") (pin "4") (pinfunction "4_4") (pintype "passive"))
      (node (ref "J13") (pin "5") (pinfunction "5_5") (pintype "passive"))
      (node (ref "J14") (pin "1") (pinfunction "1_1") (pintype "passive"))
      (node (ref "J51") (pin "1") (pinfunction "1_1") (pintype "passive"))
      (node (ref "J51") (pin "2") (pinfunction "2_2") (pintype "passive"))
      (node (ref "J51") (pin "3") (pinfunction "3_3") (pintype "passive"))
      (node (ref "J8") (pin "1") (pinfunction "1_1") (pintype "passive"))
      (node (ref "J9") (pin "1") (pinfunction "1_1") (pintype "passive"))
      (node (ref "J9") (pin "2") (pinfunction "2_2") (pintype "passive"))
      (node (ref "J9") (pin "3") (pinfunction "3_3") (pintype "passive"))
      (node (ref "J9") (pin "4") (pinfunction "4_4") (pintype "passive"))
      (node (ref "J9") (pin "5") (pinfunction "5_5") (pintype "passive"))
    )
    (net (code "3") (name "Net-(J15-Pad1)") (class "Default")
      (node (ref "J15") (pin "1") (pinfunction "1_1") (pintype "passive"))
      (node (ref "J16") (pin "1") (pinfunction "1_1") (pintype "passive"))
      (node (ref "J16") (pin "2") (pinfunction "2_2") (pintype "passive"))
      (node (ref "J16") (pin "3") (pinfunction "3_3") (pintype "passive"))
      (node (ref "J16") (pin "4") (pinfunction "4_4") (pintype "passive"))
      (node (ref "J16") (pin "5") (pinfunction "5_5") (pintype "passive"))
      (node (ref "J17") (pin "1") (pinfunction "1_1") (pintype "passive"))
      (node (ref "J17") (pin "2") (pinfunction "2_2") (pintype "passive"))
      (node (ref "J17") (pin "3") (pinfunction "3_3") (pintype "passive"))
      (node (ref "J17") (pin "4") (pinfunction "4_4") (pintype "passive"))
      (node (ref "J17") (pin "5") (pinfunction "5_5") (pintype "passive"))
      (node (ref "J18") (pin "1") (pinfunction "1_1") (pintype "passive"))
      (node (ref "J18") (pin "2") (pinfunction "2_2") (pintype "passive"))
      (node (ref "J18") (pin "3") (pinfunction "3_3") (pintype "passive"))
      (node (ref "J18") (pin "4") (pinfunction "4_4") (pintype "passive"))
      (node (ref "J18") (pin "5") (pinfunction "5_5") (pintype "passive"))
      (node (ref "J19") (pin "1") (pinfunction "1_1") (pintype "passive"))
      (node (ref "J19") (pin "2") (pinfunction "2_2") (pintype "passive"))
      (node (ref "J19") (pin "3") (pinfunction "3_3") (pintype "passive"))
      (node (ref "J19") (pin "4") (pinfunction "4_4") (pintype "passive"))
      (node (ref "J19") (pin "5") (pinfunction "5_5") (pintype "passive"))
      (node (ref "J20") (pin "1") (pinfunction "1_1") (pintype "passive"))
      (node (ref "J20") (pin "2") (pinfunction "2_2") (pintype "passive"))
      (node (ref "J20") (pin "3") (pinfunction "3_3") (pintype "passive"))
      (node (ref "J20") (pin "4") (pinfunction "4_4") (pintype "passive"))
      (node (ref "J20") (pin "5") (pinfunction "5_5") (pintype "passive"))
      (node (ref "J21") (pin "1") (pinfunction "1_1") (pintype "passive"))
      (node (ref "J54") (pin "1") (pinfunction "1_1") (pintype "passive"))
      (node (ref "J54") (pin "2") (pinfunction "2_2") (pintype "passive"))
      (node (ref "J54") (pin "3") (pinfunction "3_3") (pintype "passive"))
    )
    (net (code "4") (name "Net-(J22-Pad1)") (class "Default")
      (node (ref "J22") (pin "1") (pinfunction "1_1") (pintype "passive"))
      (node (ref "J23") (pin "1") (pinfunction "1_1") (pintype "passive"))
      (node (ref "J23") (pin "2") (pinfunction "2_2") (pintype "passive"))
      (node (ref "J23") (pin "3") (pinfunction "3_3") (pintype "passive"))
      (node (ref "J23") (pin "4") (pinfunction "4_4") (pintype "passive"))
      (node (ref "J23") (pin "5") (pinfunction "5_5") (pintype "passive"))
      (node (ref "J24") (pin "1") (pinfunction "1_1") (pintype "passive"))
      (node (ref "J24") (pin "2") (pinfunction "2_2") (pintype "passive"))
      (node (ref "J24") (pin "3") (pinfunction "3_3") (pintype "passive"))
      (node (ref "J24") (pin "4") (pinfunction "4_4") (pintype "passive"))
      (node (ref "J24") (pin "5") (pinfunction "5_5") (pintype "passive"))
      (node (ref "J25") (pin "1") (pinfunction "1_1") (pintype "passive"))
      (node (ref "J25") (pin "2") (pinfunction "2_2") (pintype "passive"))
      (node (ref "J25") (pin "3") (pinfunction "3_3") (pintype "passive"))
      (node (ref "J25") (pin "4") (pinfunction "4_4") (pintype "passive"))
      (node (ref "J25") (pin "5") (pinfunction "5_5") (pintype "passive"))
      (node (ref "J26") (pin "1") (pinfunction "1_1") (pintype "passive"))
      (node (ref "J26") (pin "2") (pinfunction "2_2") (pintype "passive"))
      (node (ref "J26") (pin "3") (pinfunction "3_3") (pintype "passive"))
      (node (ref "J26") (pin "4") (pinfunction "4_4") (pintype "passive"))
      (node (ref "J26") (pin "5") (pinfunction "5_5") (pintype "passive"))
      (node (ref "J27") (pin "1") (pinfunction "1_1") (pintype "passive"))
      (node (ref "J27") (pin "2") (pinfunction "2_2") (pintype "passive"))
      (node (ref "J27") (pin "3") (pinfunction "3_3") (pintype "passive"))
      (node (ref "J27") (pin "4") (pinfunction "4_4") (pintype "passive"))
      (node (ref "J27") (pin "5") (pinfunction "5_5") (pintype "passive"))
      (node (ref "J28") (pin "1") (pinfunction "1_1") (pintype "passive"))
      (node (ref "J53") (pin "1") (pinfunction "1_1") (pintype "passive"))
      (node (ref "J53") (pin "2") (pinfunction "2_2") (pintype "passive"))
      (node (ref "J53") (pin "3") (pinfunction "3_3") (pintype "passive"))
    )
    (net (code "5") (name "Net-(J29-Pad1)") (class "Default")
      (node (ref "J29") (pin "1") (pinfunction "1_1") (pintype "passive"))
      (node (ref "J29") (pin "2") (pinfunction "2_2") (pintype "passive"))
      (node (ref "J29") (pin "3") (pinfunction "3_3") (pintype "passive"))
      (node (ref "J29") (pin "4") (pinfunction "4_4") (pintype "passive"))
    )
    (net (code "6") (name "Net-(J30-Pad1)") (class "Default")
      (node (ref "J30") (pin "1") (pinfunction "1_1") (pintype "passive"))
      (node (ref "J30") (pin "2") (pinfunction "2_2") (pintype "passive"))
      (node (ref "J30") (pin "3") (pinfunction "3_3") (pintype "passive"))
      (node (ref "J30") (pin "4") (pinfunction "4_4") (pintype "passive"))
    )
    (net (code "7") (name "Net-(J31-Pad1)") (class "Default")
      (node (ref "J31") (pin "1") (pinfunction "1_1") (pintype "passive"))
      (node (ref "J31") (pin "2") (pinfunction "2_2") (pintype "passive"))
      (node (ref "J31") (pin "3") (pinfunction "3_3") (pintype "passive"))
      (node (ref "J31") (pin "4") (pinfunction "4_4") (pintype "passive"))
    )
    (net (code "8") (name "Net-(J32-Pad1)") (class "Default")
      (node (ref "J32") (pin "1") (pinfunction "1_1") (pintype "passive"))
      (node (ref "J32") (pin "2") (pinfunction "2_2") (pintype "passive"))
      (node (ref "J32") (pin "3") (pinfunction "3_3") (pintype "passive"))
      (node (ref "J32") (pin "4") (pinfunction "4_4") (pintype "passive"))
    )
    (net (code "9") (name "Net-(J33-Pad1)") (class "Default")
      (node (ref "J33") (pin "1") (pinfunction "1_1") (pintype "passive"))
      (node (ref "J33") (pin "2") (pinfunction "2_2") (pintype "passive"))
      (node (ref "J33") (pin "3") (pinfunction "3_3") (pintype "passive"))
      (node (ref "J33") (pin "4") (pinfunction "4_4") (pintype "passive"))
    )
    (net (code "10") (name "Net-(J34-Pad1)") (class "Default")
      (node (ref "J34") (pin "1") (pinfunction "1_1") (pintype "passive"))
      (node (ref "J34") (pin "2") (pinfunction "2_2") (pintype "passive"))
      (node (ref "J34") (pin "3") (pinfunction "3_3") (pintype "passive"))
      (node (ref "J34") (pin "4") (pinfunction "4_4") (pintype "passive"))
    )
    (net (code "11") (name "Net-(J35-Pad1)") (class "Default")
      (node (ref "J35") (pin "1") (pinfunction "1_1") (pintype "passive"))
      (node (ref "J35") (pin "2") (pinfunction "2_2") (pintype "passive"))
      (node (ref "J35") (pin "3") (pinfunction "3_3") (pintype "passive"))
      (node (ref "J35") (pin "4") (pinfunction "4_4") (pintype "passive"))
    )
    (net (code "12") (name "Net-(J36-Pad1)") (class "Default")
      (node (ref "J36") (pin "1") (pinfunction "1_1") (pintype "passive"))
      (node (ref "J36") (pin "2") (pinfunction "2_2") (pintype "passive"))
      (node (ref "J36") (pin "3") (pinfunction "3_3") (pintype "passive"))
      (node (ref "J36") (pin "4") (pinfunction "4_4") (pintype "passive"))
    )
    (net (code "13") (name "Net-(J37-Pad1)") (class "Default")
      (node (ref "J37") (pin "1") (pinfunction "1_1") (pintype "passive"))
      (node (ref "J37") (pin "2") (pinfunction "2_2") (pintype "passive"))
      (node (ref "J37") (pin "3") (pinfunction "3_3") (pintype "passive"))
      (node (ref "J37") (pin "4") (pinfunction "4_4") (pintype "passive"))
    )
    (net (code "14") (name "Net-(J38-Pad1)") (class "Default")
      (node (ref "J38") (pin "1") (pinfunction "1_1") (pintype "passive"))
      (node (ref "J38") (pin "2") (pinfunction "2_2") (pintype "passive"))
      (node (ref "J38") (pin "3") (pinfunction "3_3") (pintype "passive"))
      (node (ref "J38") (pin "4") (pinfunction "4_4") (pintype "passive"))
    )
    (net (code "15") (name "Net-(J39-Pad1)") (class "Default")
      (node (ref "J39") (pin "1") (pinfunction "1_1") (pintype "passive"))
      (node (ref "J39") (pin "2") (pinfunction "2_2") (pintype "passive"))
      (node (ref "J39") (pin "3") (pinfunction "3_3") (pintype "passive"))
      (node (ref "J39") (pin "4") (pinfunction "4_4") (pintype "passive"))
    )
    (net (code "16") (name "Net-(J40-Pad1)") (class "Default")
      (node (ref "J40") (pin "1") (pinfunction "1_1") (pintype "passive"))
      (node (ref "J40") (pin "2") (pinfunction "2_2") (pintype "passive"))
      (node (ref "J40") (pin "3") (pinfunction "3_3") (pintype "passive"))
      (node (ref "J40") (pin "4") (pinfunction "4_4") (pintype "passive"))
    )
    (net (code "17") (name "Net-(J41-Pad1)") (class "Default")
      (node (ref "J41") (pin "1") (pinfunction "1_1") (pintype "passive"))
      (node (ref "J41") (pin "2") (pinfunction "2_2") (pintype "passive"))
      (node (ref "J41") (pin "3") (pinfunction "3_3") (pintype "passive"))
      (node (ref "J41") (pin "4") (pinfunction "4_4") (pintype "passive"))
    )
    (net (code "18") (name "Net-(J42-Pad1)") (class "Default")
      (node (ref "J42") (pin "1") (pinfunction "1_1") (pintype "passive"))
      (node (ref "J42") (pin "2") (pinfunction "2_2") (pintype "passive"))
      (node (ref "J42") (pin "3") (pinfunction "3_3") (pintype "passive"))
      (node (ref "J42") (pin "4") (pinfunction "4_4") (pintype "passive"))
    )
    (net (code "19") (name "Net-(J43-Pad1)") (class "Default")
      (node (ref "J43") (pin "1") (pinfunction "1_1") (pintype "passive"))
      (node (ref "J43") (pin "2") (pinfunction "2_2") (pintype "passive"))
      (node (ref "J43") (pin "3") (pinfunction "3_3") (pintype "passive"))
      (node (ref "J43") (pin "4") (pinfunction "4_4") (pintype "passive"))
    )
    (net (code "20") (name "Net-(J44-Pad1)") (class "Default")
      (node (ref "J44") (pin "1") (pinfunction "1_1") (pintype "passive"))
      (node (ref "J44") (pin "2") (pinfunction "2_2") (pintype "passive"))
      (node (ref "J44") (pin "3") (pinfunction "3_3") (pintype "passive"))
      (node (ref "J44") (pin "4") (pinfunction "4_4") (pintype "passive"))
    )
    (net (code "21") (name "Net-(J45-Pad1)") (class "Default")
      (node (ref "J45") (pin "1") (pinfunction "1_1") (pintype "passive"))
      (node (ref "J45") (pin "2") (pinfunction "2_2") (pintype "passive"))
      (node (ref "J45") (pin "3") (pinfunction "3_3") (pintype "passive"))
      (node (ref "J45") (pin "4") (pinfunction "4_4") (pintype "passive"))
      (node (ref "J45") (pin "5") (pinfunction "5_5") (pintype "passive"))
    )
    (net (code "22") (name "Net-(J46-Pad1)") (class "Default")
      (node (ref "J46") (pin "1") (pinfunction "1_1") (pintype "passive"))
      (node (ref "J46") (pin "2") (pinfunction "2_2") (pintype "passive"))
      (node (ref "J46") (pin "3") (pinfunction "3_3") (pintype "passive"))
      (node (ref "J46") (pin "4") (pinfunction "4_4") (pintype "passive"))
      (node (ref "J46") (pin "5") (pinfunction "5_5") (pintype "passive"))
    )
    (net (code "23") (name "Net-(J47-Pad1)") (class "Default")
      (node (ref "J47") (pin "1") (pinfunction "1_1") (pintype "passive"))
      (node (ref "J47") (pin "2") (pinfunction "2_2") (pintype "passive"))
      (node (ref "J47") (pin "3") (pinfunction "3_3") (pintype "passive"))
      (node (ref "J47") (pin "4") (pinfunction "4_4") (pintype "passive"))
      (node (ref "J47") (pin "5") (pinfunction "5_5") (pintype "passive"))
    )
    (net (code "24") (name "Net-(J48-Pad1)") (class "Default")
      (node (ref "J48") (pin "1") (pinfunction "1_1") (pintype "passive"))
      (node (ref "J48") (pin "2") (pinfunction "2_2") (pintype "passive"))
      (node (ref "J48") (pin "3") (pinfunction "3_3") (pintype "passive"))
      (node (ref "J48") (pin "4") (pinfunction "4_4") (pintype "passive"))
      (node (ref "J48") (pin "5") (pinfunction "5_5") (pintype "passive"))
    )
    (net (code "25") (name "Net-(J49-Pad1)") (class "Default")
      (node (ref "J49") (pin "1") (pinfunction "1_1") (pintype "passive"))
      (node (ref "J49") (pin "2") (pinfunction "2_2") (pintype "passive"))
      (node (ref "J49") (pin "3") (pinfunction "3_3") (pintype "passive"))
      (node (ref "J49") (pin "4") (pinfunction "4_4") (pintype "passive"))
      (node (ref "J49") (pin "5") (pinfunction "5_5") (pintype "passive"))
    )
    (net (code "26") (name "Net-(J50-Pad1)") (class "Default")
      (node (ref "J50") (pin "1") (pinfunction "1_1") (pintype "passive"))
      (node (ref "J50") (pin "2") (pinfunction "2_2") (pintype "passive"))
      (node (ref "J50") (pin "3") (pinfunction "3_3") (pintype "passive"))
      (node (ref "J50") (pin "4") (pinfunction "4_4") (pintype "passive"))
      (node (ref "J50") (pin "5") (pinfunction "5_5") (pintype "passive"))
    )
    (net (code "27") (name "Net-(J61-Pad1)") (class "Default")
      (node (ref "J61") (pin "1") (pinfunction "1_1") (pintype "passive"))
      (node (ref "J61") (pin "2") (pinfunction "2_2") (pintype "passive"))
      (node (ref "J61") (pin "3") (pinfunction "3_3") (pintype "passive"))
      (node (ref "J61") (pin "4") (pinfunction "4_4") (pintype "passive"))
      (node (ref "J61") (pin "5") (pinfunction "5_5") (pintype "passive"))
    )
    (net (code "28") (name "Net-(J62-Pad1)") (class "Default")
      (node (ref "J62") (pin "1") (pinfunction "1_1") (pintype "passive"))
      (node (ref "J62") (pin "2") (pinfunction "2_2") (pintype "passive"))
      (node (ref "J62") (pin "3") (pinfunction "3_3") (pintype "passive"))
      (node (ref "J62") (pin "4") (pinfunction "4_4") (pintype "passive"))
      (node (ref "J62") (pin "5") (pinfunction "5_5") (pintype "passive"))
    )
    (net (code "29") (name "Net-(J63-Pad1)") (class "Default")
      (node (ref "J63") (pin "1") (pinfunction "1_1") (pintype "passive"))
      (node (ref "J63") (pin "2") (pinfunction "2_2") (pintype "passive"))
      (node (ref "J63") (pin "3") (pinfunction "3_3") (pintype "passive"))
      (node (ref "J63") (pin "4") (pinfunction "4_4") (pintype "passive"))
      (node (ref "J63") (pin "5") (pinfunction "5_5") (pintype "passive"))
    )
    (net (code "30") (name "Net-(J64-Pad1)") (class "Default")
      (node (ref "J64") (pin "1") (pinfunction "1_1") (pintype "passive"))
      (node (ref "J64") (pin "2") (pinfunction "2_2") (pintype "passive"))
      (node (ref "J64") (pin "3") (pinfunction "3_3") (pintype "passive"))
      (node (ref "J64") (pin "4") (pinfunction "4_4") (pintype "passive"))
      (node (ref "J64") (pin "5") (pinfunction "5_5") (pintype "passive"))
    )
    (net (code "31") (name "Net-(J65-Pad1)") (class "Default")
      (node (ref "J65") (pin "1") (pinfunction "1_1") (pintype "passive"))
      (node (ref "J65") (pin "2") (pinfunction "2_2") (pintype "passive"))
      (node (ref "J65") (pin "3") (pinfunction "3_3") (pintype "passive"))
      (node (ref "J65") (pin "4") (pinfunction "4_4") (pintype "passive"))
      (node (ref "J65") (pin "5") (pinfunction "5_5") (pintype "passive"))
    )
    (net (code "32") (name "Net-(J66-Pad1)") (class "Default")
      (node (ref "J66") (pin "1") (pinfunction "1_1") (pintype "passive"))
      (node (ref "J66") (pin "2") (pinfunction "2_2") (pintype "passive"))
      (node (ref "J66") (pin "3") (pinfunction "3_3") (pintype "passive"))
      (node (ref "J66") (pin "4") (pinfunction "4_4") (pintype "passive"))
      (node (ref "J66") (pin "5") (pinfunction "5_5") (pintype "passive"))
    )
    (net (code "33") (name "Net-(J67-Pad1)") (class "Default")
      (node (ref "J67") (pin "1") (pinfunction "1_1") (pintype "passive"))
      (node (ref "J67") (pin "2") (pinfunction "2_2") (pintype "passive"))
      (node (ref "J67") (pin "3") (pinfunction "3_3") (pintype "passive"))
      (node (ref "J67") (pin "4") (pinfunction "4_4") (pintype "passive"))
      (node (ref "J67") (pin "5") (pinfunction "5_5") (pintype "passive"))
    )
    (net (code "34") (name "Net-(J68-Pad1)") (class "Default")
      (node (ref "J68") (pin "1") (pinfunction "1_1") (pintype "passive"))
      (node (ref "J68") (pin "2") (pinfunction "2_2") (pintype "passive"))
      (node (ref "J68") (pin "3") (pinfunction "3_3") (pintype "passive"))
      (node (ref "J68") (pin "4") (pinfunction "4_4") (pintype "passive"))
      (node (ref "J68") (pin "5") (pinfunction "5_5") (pintype "passive"))
    )
    (net (code "35") (name "Net-(J69-Pad1)") (class "Default")
      (node (ref "J69") (pin "1") (pinfunction "1_1") (pintype "passive"))
      (node (ref "J69") (pin "2") (pinfunction "2_2") (pintype "passive"))
      (node (ref "J69") (pin "3") (pinfunction "3_3") (pintype "passive"))
      (node (ref "J69") (pin "4") (pinfunction "4_4") (pintype "passive"))
      (node (ref "J69") (pin "5") (pinfunction "5_5") (pintype "passive"))
    )
    (net (code "36") (name "Net-(J70-Pad1)") (class "Default")
      (node (ref "J70") (pin "1") (pinfunction "1_1") (pintype "passive"))
      (node (ref "J70") (pin "2") (pinfunction "2_2") (pintype "passive"))
      (node (ref "J70") (pin "3") (pinfunction "3_3") (pintype "passive"))
      (node (ref "J70") (pin "4") (pinfunction "4_4") (pintype "passive"))
      (node (ref "J70") (pin "5") (pinfunction "5_5") (pintype "passive"))
    )
    (net (code "37") (name "Net-(J71-Pad1)") (class "Default")
      (node (ref "J71") (pin "1") (pinfunction "1_1") (pintype "passive"))
      (node (ref "J71") (pin "2") (pinfunction "2_2") (pintype "passive"))
      (node (ref "J71") (pin "3") (pinfunction "3_3") (pintype "passive"))
      (node (ref "J71") (pin "4") (pinfunction "4_4") (pintype "passive"))
      (node (ref "J71") (pin "5") (pinfunction "5_5") (pintype "passive"))
    )
    (net (code "38") (name "Net-(J72-Pad1)") (class "Default")
      (node (ref "J72") (pin "1") (pinfunction "1_1") (pintype "passive"))
      (node (ref "J72") (pin "2") (pinfunction "2_2") (pintype "passive"))
      (node (ref "J72") (pin "3") (pinfunction "3_3") (pintype "passive"))
      (node (ref "J72") (pin "4") (pinfunction "4_4") (pintype "passive"))
      (node (ref "J72") (pin "5") (pinfunction "5_5") (pintype "passive"))
    )
    (net (code "39") (name "Net-(J73-Pad1)") (class "Default")
      (node (ref "J73") (pin "1") (pinfunction "1_1") (pintype "passive"))
      (node (ref "J73") (pin "2") (pinfunction "2_2") (pintype "passive"))
      (node (ref "J73") (pin "3") (pinfunction "3_3") (pintype "passive"))
      (node (ref "J73") (pin "4") (pinfunction "4_4") (pintype "passive"))
      (node (ref "J73") (pin "5") (pinfunction "5_5") (pintype "passive"))
    )
    (net (code "40") (name "Net-(J74-Pad1)") (class "Default")
      (node (ref "J74") (pin "1") (pinfunction "1_1") (pintype "passive"))
      (node (ref "J74") (pin "2") (pinfunction "2_2") (pintype "passive"))
      (node (ref "J74") (pin "3") (pinfunction "3_3") (pintype "passive"))
      (node (ref "J74") (pin "4") (pinfunction "4_4") (pintype "passive"))
      (node (ref "J74") (pin "5") (pinfunction "5_5") (pintype "passive"))
    )
    (net (code "41") (name "Net-(J75-Pad1)") (class "Default")
      (node (ref "J75") (pin "1") (pinfunction "1_1") (pintype "passive"))
      (node (ref "J75") (pin "2") (pinfunction "2_2") (pintype "passive"))
      (node (ref "J75") (pin "3") (pinfunction "3_3") (pintype "passive"))
      (node (ref "J75") (pin "4") (pinfunction "4_4") (pintype "passive"))
      (node (ref "J75") (pin "5") (pinfunction "5_5") (pintype "passive"))
    )
    (net (code "42") (name "Net-(J76-Pad1)") (class "Default")
      (node (ref "J76") (pin "1") (pinfunction "1_1") (pintype "passive"))
      (node (ref "J76") (pin "2") (pinfunction "2_2") (pintype "passive"))
      (node (ref "J76") (pin "3") (pinfunction "3_3") (pintype "passive"))
      (node (ref "J76") (pin "4") (pinfunction "4_4") (pintype "passive"))
      (node (ref "J76") (pin "5") (pinfunction "5_5") (pintype "passive"))
    )
    (net (code "43") (name "Net-(J77-Pad1)") (class "Default")
      (node (ref "J77") (pin "1") (pinfunction "1_1") (pintype "passive"))
      (node (ref "J77") (pin "2") (pinfunction "2_2") (pintype "passive"))
      (node (ref "J77") (pin "3") (pinfunction "3_3") (pintype "passive"))
      (node (ref "J77") (pin "4") (pinfunction "4_4") (pintype "passive"))
      (node (ref "J77") (pin "5") (pinfunction "5_5") (pintype "passive"))
    )
    (net (code "44") (name "Net-(J78-Pad1)") (class "Default")
      (node (ref "J78") (pin "1") (pinfunction "1_1") (pintype "passive"))
      (node (ref "J78") (pin "2") (pinfunction "2_2") (pintype "passive"))
      (node (ref "J78") (pin "3") (pinfunction "3_3") (pintype "passive"))
      (node (ref "J78") (pin "4") (pinfunction "4_4") (pintype "passive"))
      (node (ref "J78") (pin "5") (pinfunction "5_5") (pintype "passive"))
    )
    (net (code "45") (name "Net-(J79-Pad1)") (class "Default")
      (node (ref "J79") (pin "1") (pinfunction "1_1") (pintype "passive"))
      (node (ref "J79") (pin "2") (pinfunction "2_2") (pintype "passive"))
      (node (ref "J79") (pin "3") (pinfunction "3_3") (pintype "passive"))
      (node (ref "J79") (pin "4") (pinfunction "4_4") (pintype "passive"))
      (node (ref "J79") (pin "5") (pinfunction "5_5") (pintype "passive"))
    )
    (net (code "46") (name "Net-(J80-Pad1)") (class "Default")
      (node (ref "J80") (pin "1") (pinfunction "1_1") (pintype "passive"))
      (node (ref "J80") (pin "2") (pinfunction "2_2") (pintype "passive"))
      (node (ref "J80") (pin "3") (pinfunction "3_3") (pintype "passive"))
      (node (ref "J80") (pin "4") (pinfunction "4_4") (pintype "passive"))
      (node (ref "J80") (pin "5") (pinfunction "5_5") (pintype "passive"))
    )
    (net (code "47") (name "Net-(J81-Pad1)") (class "Default")
      (node (ref "J81") (pin "1") (pinfunction "1_1") (pintype "passive"))
      (node (ref "J81") (pin "2") (pinfunction "2_2") (pintype "passive"))
      (node (ref "J81") (pin "3") (pinfunction "3_3") (pintype "passive"))
      (node (ref "J81") (pin "4") (pinfunction "4_4") (pintype "passive"))
      (node (ref "J81") (pin "5") (pinfunction "5_5") (pintype "passive"))
    )
    (net (code "48") (name "Net-(J82-Pad1)") (class "Default")
      (node (ref "J82") (pin "1") (pinfunction "1_1") (pintype "passive"))
      (node (ref "J82") (pin "2") (pinfunction "2_2") (pintype "passive"))
      (node (ref "J82") (pin "3") (pinfunction "3_3") (pintype "passive"))
      (node (ref "J82") (pin "4") (pinfunction "4_4") (pintype "passive"))
      (node (ref "J82") (pin "5") (pinfunction "5_5") (pintype "passive"))
    )
    (net (code "49") (name "Net-(J83-Pad1)") (class "Default")
      (node (ref "J83") (pin "1") (pinfunction "1_1") (pintype "passive"))
      (node (ref "J83") (pin "2") (pinfunction "2_2") (pintype "passive"))
      (node (ref "J83") (pin "3") (pinfunction "3_3") (pintype "passive"))
      (node (ref "J83") (pin "4") (pinfunction "4_4") (pintype "passive"))
      (node (ref "J83") (pin "5") (pinfunction "5_5") (pintype "passive"))
    )
    (net (code "50") (name "Net-(J84-Pad1)") (class "Default")
      (node (ref "J84") (pin "1") (pinfunction "1_1") (pintype "passive"))
      (node (ref "J84") (pin "2") (pinfunction "2_2") (pintype "passive"))
      (node (ref "J84") (pin "3") (pinfunction "3_3") (pintype "passive"))
      (node (ref "J84") (pin "4") (pinfunction "4_4") (pintype "passive"))
      (node (ref "J84") (pin "5") (pinfunction "5_5") (pintype "passive"))
    )
    (net (code "51") (name "Net-(J85-Pad1)") (class "Default")
      (node (ref "J85") (pin "1") (pinfunction "1_1") (pintype "passive"))
      (node (ref "J85") (pin "2") (pinfunction "2_2") (pintype "passive"))
      (node (ref "J85") (pin "3") (pinfunction "3_3") (pintype "passive"))
      (node (ref "J85") (pin "4") (pinfunction "4_4") (pintype "passive"))
      (node (ref "J85") (pin "5") (pinfunction "5_5") (pintype "passive"))
    )
    (net (code "52") (name "Net-(J86-Pad1)") (class "Default")
      (node (ref "J86") (pin "1") (pinfunction "1_1") (pintype "passive"))
      (node (ref "J86") (pin "2") (pinfunction "2_2") (pintype "passive"))
      (node (ref "J86") (pin "3") (pinfunction "3_3") (pintype "passive"))
      (node (ref "J86") (pin "4") (pinfunction "4_4") (pintype "passive"))
      (node (ref "J86") (pin "5") (pinfunction "5_5") (pintype "passive"))
    )
    (net (code "53") (name "Net-(J87-Pad1)") (class "Default")
      (node (ref "J87") (pin "1") (pinfunction "1_1") (pintype "passive"))
      (node (ref "J87") (pin "2") (pinfunction "2_2") (pintype "passive"))
      (node (ref "J87") (pin "3") (pinfunction "3_3") (pintype "passive"))
      (node (ref "J87") (pin "4") (pinfunction "4_4") (pintype "passive"))
      (node (ref "J87") (pin "5") (pinfunction "5_5") (pintype "passive"))
    )
    (net (code "54") (name "Net-(J96-Pad1)") (class "Default")
      (node (ref "J96") (pin "1") (pinfunction "1_1") (pintype "passive"))
      (node (ref "J96") (pin "2") (pinfunction "2_2") (pintype "passive"))
      (node (ref "J96") (pin "3") (pinfunction "3_3") (pintype "passive"))
      (node (ref "J96") (pin "4") (pinfunction "4_4") (pintype "passive"))
      (node (ref "J96") (pin "5") (pinfunction "5_5") (pintype "passive"))
    )
    (net (code "55") (name "Net-(J97-Pad1)") (class "Default")
      (node (ref "J97") (pin "1") (pinfunction "1_1") (pintype "passive"))
      (node (ref "J97") (pin "2") (pinfunction "2_2") (pintype "passive"))
      (node (ref "J97") (pin "3") (pinfunction "3_3") (pintype "passive"))
      (node (ref "J97") (pin "4") (pinfunction "4_4") (pintype "passive"))
      (node (ref "J97") (pin "5") (pinfunction "5_5") (pintype "passive"))
    )
    (net (code "56") (name "Net-(J98-Pad1)") (class "Default")
      (node (ref "J98") (pin "1") (pinfunction "1_1") (pintype "passive"))
      (node (ref "J98") (pin "2") (pinfunction "2_2") (pintype "passive"))
      (node (ref "J98") (pin "3") (pinfunction "3_3") (pintype "passive"))
      (node (ref "J98") (pin "4") (pinfunction "4_4") (pintype "passive"))
      (node (ref "J98") (pin "5") (pinfunction "5_5") (pintype "passive"))
    )
    (net (code "57") (name "Net-(J99-Pad1)") (class "Default")
      (node (ref "J99") (pin "1") (pinfunction "1_1") (pintype "passive"))
      (node (ref "J99") (pin "2") (pinfunction "2_2") (pintype "passive"))
      (node (ref "J99") (pin "3") (pinfunction "3_3") (pintype "passive"))
      (node (ref "J99") (pin "4") (pinfunction "4_4") (pintype "passive"))
      (node (ref "J99") (pin "5") (pinfunction "5_5") (pintype "passive"))
    )
    (net (code "58") (name "Net-(J100-Pad1)") (class "Default")
      (node (ref "J100") (pin "1") (pinfunction "1_1") (pintype "passive"))
      (node (ref "J100") (pin "2") (pinfunction "2_2") (pintype "passive"))
      (node (ref "J100") (pin "3") (pinfunction "3_3") (pintype "passive"))
      (node (ref "J100") (pin "4") (pinfunction "4_4") (pintype "passive"))
      (node (ref "J100") (pin "5") (pinfunction "5_5") (pintype "passive"))
    )
    (net (code "59") (name "Net-(J101-Pad1)") (class "Default")
      (node (ref "J101") (pin "1") (pinfunction "1_1") (pintype "passive"))
      (node (ref "J101") (pin "2") (pinfunction "2_2") (pintype "passive"))
      (node (ref "J101") (pin "3") (pinfunction "3_3") (pintype "passive"))
      (node (ref "J101") (pin "4") (pinfunction "4_4") (pintype "passive"))
      (node (ref "J101") (pin "5") (pinfunction "5_5") (pintype "passive"))
    )
    (net (code "60") (name "Net-(J102-Pad1)") (class "Default")
      (node (ref "J102") (pin "1") (pinfunction "1_1") (pintype "passive"))
      (node (ref "J102") (pin "2") (pinfunction "2_2") (pintype "passive"))
      (node (ref "J102") (pin "3") (pinfunction "3_3") (pintype "passive"))
      (node (ref "J102") (pin "4") (pinfunction "4_4") (pintype "passive"))
      (node (ref "J102") (pin "5") (pinfunction "5_5") (pintype "passive"))
    )
    (net (code "61") (name "Net-(J103-Pad1)") (class "Default")
      (node (ref "J103") (pin "1") (pinfunction "1_1") (pintype "passive"))
      (node (ref "J103") (pin "2") (pinfunction "2_2") (pintype "passive"))
      (node (ref "J103") (pin "3") (pinfunction "3_3") (pintype "passive"))
      (node (ref "J103") (pin "4") (pinfunction "4_4") (pintype "passive"))
      (node (ref "J103") (pin "5") (pinfunction "5_5") (pintype "passive"))
    )
    (net (code "62") (name "Net-(J104-Pad1)") (class "Default")
      (node (ref "J104") (pin "1") (pinfunction "1_1") (pintype "passive"))
      (node (ref "J104") (pin "2") (pinfunction "2_2") (pintype "passive"))
      (node (ref "J104") (pin "3") (pinfunction "3_3") (pintype "passive"))
      (node (ref "J104") (pin "4") (pinfunction "4_4") (pintype "passive"))
      (node (ref "J104") (pin "5") (pinfunction "5_5") (pintype "passive"))
    )
    (net (code "63") (name "Net-(J105-Pad1)") (class "Default")
      (node (ref "J105") (pin "1") (pinfunction "1_1") (pintype "passive"))
      (node (ref "J105") (pin "2") (pinfunction "2_2") (pintype "passive"))
      (node (ref "J105") (pin "3") (pinfunction "3_3") (pintype "passive"))
      (node (ref "J105") (pin "4") (pinfunction "4_4") (pintype "passive"))
      (node (ref "J105") (pin "5") (pinfunction "5_5") (pintype "passive"))
    )
    (net (code "64") (name "Net-(J106-Pad1)") (class "Default")
      (node (ref "J106") (pin "1") (pinfunction "1_1") (pintype "passive"))
      (node (ref "J106") (pin "2") (pinfunction "2_2") (pintype "passive"))
      (node (ref "J106") (pin "3") (pinfunction "3_3") (pintype "passive"))
      (node (ref "J106") (pin "4") (pinfunction "4_4") (pintype "passive"))
      (node (ref "J106") (pin "5") (pinfunction "5_5") (pintype "passive"))
    )
    (net (code "65") (name "Net-(J107-Pad1)") (class "Default")
      (node (ref "J107") (pin "1") (pinfunction "1_1") (pintype "passive"))
      (node (ref "J107") (pin "2") (pinfunction "2_2") (pintype "passive"))
      (node (ref "J107") (pin "3") (pinfunction "3_3") (pintype "passive"))
      (node (ref "J107") (pin "4") (pinfunction "4_4") (pintype "passive"))
      (node (ref "J107") (pin "5") (pinfunction "5_5") (pintype "passive"))
    )
    (net (code "66") (name "Net-(J108-Pad1)") (class "Default")
      (node (ref "J108") (pin "1") (pinfunction "1_1") (pintype "passive"))
      (node (ref "J108") (pin "2") (pinfunction "2_2") (pintype "passive"))
      (node (ref "J108") (pin "3") (pinfunction "3_3") (pintype "passive"))
      (node (ref "J108") (pin "4") (pinfunction "4_4") (pintype "passive"))
      (node (ref "J108") (pin "5") (pinfunction "5_5") (pintype "passive"))
    )
    (net (code "67") (name "Net-(J109-Pad1)") (class "Default")
      (node (ref "J109") (pin "1") (pinfunction "1_1") (pintype "passive"))
      (node (ref "J109") (pin "2") (pinfunction "2_2") (pintype "passive"))
      (node (ref "J109") (pin "3") (pinfunction "3_3") (pintype "passive"))
      (node (ref "J109") (pin "4") (pinfunction "4_4") (pintype "passive"))
      (node (ref "J109") (pin "5") (pinfunction "5_5") (pintype "passive"))
    )
    (net (code "68") (name "Net-(J110-Pad1)") (class "Default")
      (node (ref "J110") (pin "1") (pinfunction "1_1") (pintype "passive"))
      (node (ref "J110") (pin "2") (pinfunction "2_2") (pintype "passive"))
      (node (ref "J110") (pin "3") (pinfunction "3_3") (pintype "passive"))
      (node (ref "J110") (pin "4") (pinfunction "4_4") (pintype "passive"))
      (node (ref "J110") (pin "5") (pinfunction "5_5") (pintype "passive"))
    )
    (net (code "69") (name "Net-(J111-Pad1)") (class "Default")
      (node (ref "J111") (pin "1") (pinfunction "1_1") (pintype "passive"))
      (node (ref "J111") (pin "2") (pinfunction "2_2") (pintype "passive"))
      (node (ref "J111") (pin "3") (pinfunction "3_3") (pintype "passive"))
      (node (ref "J111") (pin "4") (pinfunction "4_4") (pintype "passive"))
      (node (ref "J111") (pin "5") (pinfunction "5_5") (pintype "passive"))
    )
    (net (code "70") (name "Net-(J112-Pad1)") (class "Default")
      (node (ref "J112") (pin "1") (pinfunction "1_1") (pintype "passive"))
      (node (ref "J112") (pin "2") (pinfunction "2_2") (pintype "passive"))
      (node (ref "J112") (pin "3") (pinfunction "3_3") (pintype "passive"))
      (node (ref "J112") (pin "4") (pinfunction "4_4") (pintype "passive"))
      (node (ref "J112") (pin "5") (pinfunction "5_5") (pintype "passive"))
    )
    (net (code "71") (name "Net-(J113-Pad1)") (class "Default")
      (node (ref "J113") (pin "1") (pinfunction "1_1") (pintype "passive"))
      (node (ref "J113") (pin "2") (pinfunction "2_2") (pintype "passive"))
      (node (ref "J113") (pin "3") (pinfunction "3_3") (pintype "passive"))
      (node (ref "J113") (pin "4") (pinfunction "4_4") (pintype "passive"))
      (node (ref "J113") (pin "5") (pinfunction "5_5") (pintype "passive"))
    )
    (net (code "72") (name "Net-(J114-Pad1)") (class "Default")
      (node (ref "J114") (pin "1") (pinfunction "1_1") (pintype "passive"))
      (node (ref "J114") (pin "2") (pinfunction "2_2") (pintype "passive"))
      (node (ref "J114") (pin "3") (pinfunction "3_3") (pintype "passive"))
      (node (ref "J114") (pin "4") (pinfunction "4_4") (pintype "passive"))
      (node (ref "J114") (pin "5") (pinfunction "5_5") (pintype "passive"))
    )
    (net (code "73") (name "Net-(J115-Pad1)") (class "Default")
      (node (ref "J115") (pin "1") (pinfunction "1_1") (pintype "passive"))
      (node (ref "J115") (pin "2") (pinfunction "2_2") (pintype "passive"))
      (node (ref "J115") (pin "3") (pinfunction "3_3") (pintype "passive"))
      (node (ref "J115") (pin "4") (pinfunction "4_4") (pintype "passive"))
      (node (ref "J115") (pin "5") (pinfunction "5_5") (pintype "passive"))
    )
    (net (code "74") (name "Net-(J116-Pad1)") (class "Default")
      (node (ref "J116") (pin "1") (pinfunction "1_1") (pintype "passive"))
      (node (ref "J116") (pin "2") (pinfunction "2_2") (pintype "passive"))
      (node (ref "J116") (pin "3") (pinfunction "3_3") (pintype "passive"))
      (node (ref "J116") (pin "4") (pinfunction "4_4") (pintype "passive"))
      (node (ref "J116") (pin "5") (pinfunction "5_5") (pintype "passive"))
    )
    (net (code "75") (name "Net-(J117-Pad1)") (class "Default")
      (node (ref "J117") (pin "1") (pinfunction "1_1") (pintype "passive"))
      (node (ref "J117") (pin "2") (pinfunction "2_2") (pintype "passive"))
      (node (ref "J117") (pin "3") (pinfunction "3_3") (pintype "passive"))
      (node (ref "J117") (pin "4") (pinfunction "4_4") (pintype "passive"))
      (node (ref "J117") (pin "5") (pinfunction "5_5") (pintype "passive"))
    )
    (net (code "76") (name "Net-(J118-Pad1)") (class "Default")
      (node (ref "J118") (pin "1") (pinfunction "1_1") (pintype "passive"))
      (node (ref "J118") (pin "2") (pinfunction "2_2") (pintype "passive"))
      (node (ref "J118") (pin "3") (pinfunction "3_3") (pintype "passive"))
      (node (ref "J118") (pin "4") (pinfunction "4_4") (pintype "passive"))
      (node (ref "J118") (pin "5") (pinfunction "5_5") (pintype "passive"))
    )
    (net (code "77") (name "Net-(J119-Pad1)") (class "Default")
      (node (ref "J119") (pin "1") (pinfunction "1_1") (pintype "passive"))
      (node (ref "J119") (pin "2") (pinfunction "2_2") (pintype "passive"))
      (node (ref "J119") (pin "3") (pinfunction "3_3") (pintype "passive"))
      (node (ref "J119") (pin "4") (pinfunction "4_4") (pintype "passive"))
      (node (ref "J119") (pin "5") (pinfunction "5_5") (pintype "passive"))
    )
    (net (code "78") (name "Net-(J120-Pad1)") (class "Default")
      (node (ref "J120") (pin "1") (pinfunction "1_1") (pintype "passive"))
      (node (ref "J120") (pin "2") (pinfunction "2_2") (pintype "passive"))
      (node (ref "J120") (pin "3") (pinfunction "3_3") (pintype "passive"))
      (node (ref "J120") (pin "4") (pinfunction "4_4") (pintype "passive"))
      (node (ref "J120") (pin "5") (pinfunction "5_5") (pintype "passive"))
    )
    (net (code "79") (name "Net-(J121-Pad1)") (class "Default")
      (node (ref "J121") (pin "1") (pinfunction "1_1") (pintype "passive"))
      (node (ref "J121") (pin "2") (pinfunction "2_2") (pintype "passive"))
      (node (ref "J121") (pin "3") (pinfunction "3_3") (pintype "passive"))
      (node (ref "J121") (pin "4") (pinfunction "4_4") (pintype "passive"))
      (node (ref "J121") (pin "5") (pinfunction "5_5") (pintype "passive"))
    )
    (net (code "80") (name "Net-(J122-Pad1)") (class "Default")
      (node (ref "J122") (pin "1") (pinfunction "1_1") (pintype "passive"))
      (node (ref "J122") (pin "2") (pinfunction "2_2") (pintype "passive"))
      (node (ref "J122") (pin "3") (pinfunction "3_3") (pintype "passive"))
      (node (ref "J122") (pin "4") (pinfunction "4_4") (pintype "passive"))
      (node (ref "J122") (pin "5") (pinfunction "5_5") (pintype "passive"))
    )
    (net (code "81") (name "Net-(J123-Pad1)") (class "Default")
      (node (ref "J123") (pin "1") (pinfunction "1_1") (pintype "passive"))
      (node (ref "J123") (pin "2") (pinfunction "2_2") (pintype "passive"))
      (node (ref "J123") (pin "3") (pinfunction "3_3") (pintype "passive"))
      (node (ref "J123") (pin "4") (pinfunction "4_4") (pintype "passive"))
      (node (ref "J123") (pin "5") (pinfunction "5_5") (pintype "passive"))
      (node (ref "J183") (pin "1") (pinfunction "1_1") (pintype "passive"))
      (node (ref "J195") (pin "1") (pinfunction "1_1") (pintype "passive"))
      (node (ref "J216") (pin "1") (pinfunction "1_1") (pintype "passive"))
      (node (ref "J216") (pin "2") (pinfunction "2_2") (pintype "passive"))
      (node (ref "J216") (pin "3") (pinfunction "3_3") (pintype "passive"))
      (node (ref "J92") (pin "1") (pinfunction "1_1") (pintype "passive"))
      (node (ref "J92") (pin "2") (pinfunction "2_2") (pintype "passive"))
      (node (ref "J92") (pin "3") (pinfunction "3_3") (pintype "passive"))
      (node (ref "J92") (pin "4") (pinfunction "4_4") (pintype "passive"))
      (node (ref "J92") (pin "5") (pinfunction "5_5") (pintype "passive"))
      (node (ref "J93") (pin "1") (pinfunction "1_1") (pintype "passive"))
      (node (ref "J93") (pin "2") (pinfunction "2_2") (pintype "passive"))
      (node (ref "J93") (pin "3") (pinfunction "3_3") (pintype "passive"))
      (node (ref "J93") (pin "4") (pinfunction "4_4") (pintype "passive"))
      (node (ref "J93") (pin "5") (pinfunction "5_5") (pintype "passive"))
      (node (ref "J94") (pin "1") (pinfunction "1_1") (pintype "passive"))
      (node (ref "J94") (pin "2") (pinfunction "2_2") (pintype "passive"))
      (node (ref "J94") (pin "3") (pinfunction "3_3") (pintype "passive"))
      (node (ref "J94") (pin "4") (pinfunction "4_4") (pintype "passive"))
      (node (ref "J94") (pin "5") (pinfunction "5_5") (pintype "passive"))
      (node (ref "J95") (pin "1") (pinfunction "1_1") (pintype "passive"))
      (node (ref "J95") (pin "2") (pinfunction "2_2") (pintype "passive"))
      (node (ref "J95") (pin "3") (pinfunction "3_3") (pintype "passive"))
      (node (ref "J95") (pin "4") (pinfunction "4_4") (pintype "passive"))
      (node (ref "J95") (pin "5") (pinfunction "5_5") (pintype "passive"))
    )
    (net (code "82") (name "Net-(J124-Pad1)") (class "Default")
      (node (ref "J124") (pin "1") (pinfunction "1_1") (pintype "passive"))
      (node (ref "J124") (pin "2") (pinfunction "2_2") (pintype "passive"))
      (node (ref "J124") (pin "3") (pinfunction "3_3") (pintype "passive"))
      (node (ref "J124") (pin "4") (pinfunction "4_4") (pintype "passive"))
      (node (ref "J124") (pin "5") (pinfunction "5_5") (pintype "passive"))
      (node (ref "J125") (pin "1") (pinfunction "1_1") (pintype "passive"))
      (node (ref "J125") (pin "2") (pinfunction "2_2") (pintype "passive"))
      (node (ref "J125") (pin "3") (pinfunction "3_3") (pintype "passive"))
      (node (ref "J125") (pin "4") (pinfunction "4_4") (pintype "passive"))
      (node (ref "J125") (pin "5") (pinfunction "5_5") (pintype "passive"))
      (node (ref "J126") (pin "1") (pinfunction "1_1") (pintype "passive"))
      (node (ref "J126") (pin "2") (pinfunction "2_2") (pintype "passive"))
      (node (ref "J126") (pin "3") (pinfunction "3_3") (pintype "passive"))
      (node (ref "J126") (pin "4") (pinfunction "4_4") (pintype "passive"))
      (node (ref "J126") (pin "5") (pinfunction "5_5") (pintype "passive"))
      (node (ref "J127") (pin "1") (pinfunction "1_1") (pintype "passive"))
      (node (ref "J127") (pin "2") (pinfunction "2_2") (pintype "passive"))
      (node (ref "J127") (pin "3") (pinfunction "3_3") (pintype "passive"))
      (node (ref "J127") (pin "4") (pinfunction "4_4") (pintype "passive"))
      (node (ref "J127") (pin "5") (pinfunction "5_5") (pintype "passive"))
      (node (ref "J128") (pin "1") (pinfunction "1_1") (pintype "passive"))
      (node (ref "J128") (pin "2") (pinfunction "2_2") (pintype "passive"))
      (node (ref "J128") (pin "3") (pinfunction "3_3") (pintype "passive"))
      (node (ref "J128") (pin "4") (pinfunction "4_4") (pintype "passive"))
      (node (ref "J128") (pin "5") (pinfunction "5_5") (pintype "passive"))
      (node (ref "J184") (pin "1") (pinfunction "1_1") (pintype "passive"))
      (node (ref "J196") (pin "1") (pinfunction "1_1") (pintype "passive"))
      (node (ref "J215") (pin "1") (pinfunction "1_1") (pintype "passive"))
      (node (ref "J215") (pin "2") (pinfunction "2_2") (pintype "passive"))
      (node (ref "J215") (pin "3") (pinfunction "3_3") (pintype "passive"))
    )
    (net (code "83") (name "Net-(J129-Pad1)") (class "Default")
      (node (ref "J129") (pin "1") (pinfunction "1_1") (pintype "passive"))
      (node (ref "J129") (pin "2") (pinfunction "2_2") (pintype "passive"))
      (node (ref "J129") (pin "3") (pinfunction "3_3") (pintype "passive"))
      (node (ref "J129") (pin "4") (pinfunction "4_4") (pintype "passive"))
      (node (ref "J129") (pin "5") (pinfunction "5_5") (pintype "passive"))
    )
    (net (code "84") (name "Net-(J130-Pad1)") (class "Default")
      (node (ref "J130") (pin "1") (pinfunction "1_1") (pintype "passive"))
      (node (ref "J130") (pin "2") (pinfunction "2_2") (pintype "passive"))
      (node (ref "J130") (pin "3") (pinfunction "3_3") (pintype "passive"))
      (node (ref "J130") (pin "4") (pinfunction "4_4") (pintype "passive"))
      (node (ref "J130") (pin "5") (pinfunction "5_5") (pintype "passive"))
    )
    (net (code "85") (name "Net-(J131-Pad1)") (class "Default")
      (node (ref "J131") (pin "1") (pinfunction "1_1") (pintype "passive"))
      (node (ref "J131") (pin "2") (pinfunction "2_2") (pintype "passive"))
      (node (ref "J131") (pin "3") (pinfunction "3_3") (pintype "passive"))
      (node (ref "J131") (pin "4") (pinfunction "4_4") (pintype "passive"))
      (node (ref "J131") (pin "5") (pinfunction "5_5") (pintype "passive"))
    )
    (net (code "86") (name "Net-(J132-Pad1)") (class "Default")
      (node (ref "J132") (pin "1") (pinfunction "1_1") (pintype "passive"))
      (node (ref "J132") (pin "2") (pinfunction "2_2") (pintype "passive"))
      (node (ref "J132") (pin "3") (pinfunction "3_3") (pintype "passive"))
      (node (ref "J132") (pin "4") (pinfunction "4_4") (pintype "passive"))
      (node (ref "J132") (pin "5") (pinfunction "5_5") (pintype "passive"))
    )
    (net (code "87") (name "Net-(J133-Pad1)") (class "Default")
      (node (ref "J133") (pin "1") (pinfunction "1_1") (pintype "passive"))
      (node (ref "J133") (pin "2") (pinfunction "2_2") (pintype "passive"))
      (node (ref "J133") (pin "3") (pinfunction "3_3") (pintype "passive"))
      (node (ref "J133") (pin "4") (pinfunction "4_4") (pintype "passive"))
      (node (ref "J133") (pin "5") (pinfunction "5_5") (pintype "passive"))
    )
    (net (code "88") (name "Net-(J134-Pad1)") (class "Default")
      (node (ref "J134") (pin "1") (pinfunction "1_1") (pintype "passive"))
      (node (ref "J134") (pin "2") (pinfunction "2_2") (pintype "passive"))
      (node (ref "J134") (pin "3") (pinfunction "3_3") (pintype "passive"))
      (node (ref "J134") (pin "4") (pinfunction "4_4") (pintype "passive"))
      (node (ref "J134") (pin "5") (pinfunction "5_5") (pintype "passive"))
    )
    (net (code "89") (name "Net-(J135-Pad1)") (class "Default")
      (node (ref "J135") (pin "1") (pinfunction "1_1") (pintype "passive"))
      (node (ref "J135") (pin "2") (pinfunction "2_2") (pintype "passive"))
      (node (ref "J135") (pin "3") (pinfunction "3_3") (pintype "passive"))
      (node (ref "J135") (pin "4") (pinfunction "4_4") (pintype "passive"))
      (node (ref "J135") (pin "5") (pinfunction "5_5") (pintype "passive"))
    )
    (net (code "90") (name "Net-(J136-Pad1)") (class "Default")
      (node (ref "J136") (pin "1") (pinfunction "1_1") (pintype "passive"))
      (node (ref "J136") (pin "2") (pinfunction "2_2") (pintype "passive"))
      (node (ref "J136") (pin "3") (pinfunction "3_3") (pintype "passive"))
      (node (ref "J136") (pin "4") (pinfunction "4_4") (pintype "passive"))
      (node (ref "J136") (pin "5") (pinfunction "5_5") (pintype "passive"))
    )
    (net (code "91") (name "Net-(J137-Pad1)") (class "Default")
      (node (ref "J137") (pin "1") (pinfunction "1_1") (pintype "passive"))
      (node (ref "J137") (pin "2") (pinfunction "2_2") (pintype "passive"))
      (node (ref "J137") (pin "3") (pinfunction "3_3") (pintype "passive"))
      (node (ref "J137") (pin "4") (pinfunction "4_4") (pintype "passive"))
      (node (ref "J137") (pin "5") (pinfunction "5_5") (pintype "passive"))
    )
    (net (code "92") (name "Net-(J138-Pad1)") (class "Default")
      (node (ref "J138") (pin "1") (pinfunction "1_1") (pintype "passive"))
      (node (ref "J138") (pin "2") (pinfunction "2_2") (pintype "passive"))
      (node (ref "J138") (pin "3") (pinfunction "3_3") (pintype "passive"))
      (node (ref "J138") (pin "4") (pinfunction "4_4") (pintype "passive"))
      (node (ref "J138") (pin "5") (pinfunction "5_5") (pintype "passive"))
    )
    (net (code "93") (name "Net-(J139-Pad1)") (class "Default")
      (node (ref "J139") (pin "1") (pinfunction "1_1") (pintype "passive"))
      (node (ref "J139") (pin "2") (pinfunction "2_2") (pintype "passive"))
      (node (ref "J139") (pin "3") (pinfunction "3_3") (pintype "passive"))
      (node (ref "J139") (pin "4") (pinfunction "4_4") (pintype "passive"))
      (node (ref "J139") (pin "5") (pinfunction "5_5") (pintype "passive"))
    )
    (net (code "94") (name "Net-(J140-Pad1)") (class "Default")
      (node (ref "J140") (pin "1") (pinfunction "1_1") (pintype "passive"))
      (node (ref "J140") (pin "2") (pinfunction "2_2") (pintype "passive"))
      (node (ref "J140") (pin "3") (pinfunction "3_3") (pintype "passive"))
      (node (ref "J140") (pin "4") (pinfunction "4_4") (pintype "passive"))
      (node (ref "J140") (pin "5") (pinfunction "5_5") (pintype "passive"))
    )
    (net (code "95") (name "Net-(J141-Pad1)") (class "Default")
      (node (ref "J141") (pin "1") (pinfunction "1_1") (pintype "passive"))
      (node (ref "J141") (pin "2") (pinfunction "2_2") (pintype "passive"))
      (node (ref "J141") (pin "3") (pinfunction "3_3") (pintype "passive"))
      (node (ref "J141") (pin "4") (pinfunction "4_4") (pintype "passive"))
      (node (ref "J141") (pin "5") (pinfunction "5_5") (pintype "passive"))
    )
    (net (code "96") (name "Net-(J142-Pad1)") (class "Default")
      (node (ref "J142") (pin "1") (pinfunction "1_1") (pintype "passive"))
      (node (ref "J142") (pin "2") (pinfunction "2_2") (pintype "passive"))
      (node (ref "J142") (pin "3") (pinfunction "3_3") (pintype "passive"))
      (node (ref "J142") (pin "4") (pinfunction "4_4") (pintype "passive"))
      (node (ref "J142") (pin "5") (pinfunction "5_5") (pintype "passive"))
    )
    (net (code "97") (name "Net-(J143-Pad1)") (class "Default")
      (node (ref "J143") (pin "1") (pinfunction "1_1") (pintype "passive"))
      (node (ref "J143") (pin "2") (pinfunction "2_2") (pintype "passive"))
      (node (ref "J143") (pin "3") (pinfunction "3_3") (pintype "passive"))
      (node (ref "J143") (pin "4") (pinfunction "4_4") (pintype "passive"))
      (node (ref "J143") (pin "5") (pinfunction "5_5") (pintype "passive"))
    )
    (net (code "98") (name "Net-(J144-Pad1)") (class "Default")
      (node (ref "J144") (pin "1") (pinfunction "1_1") (pintype "passive"))
      (node (ref "J144") (pin "2") (pinfunction "2_2") (pintype "passive"))
      (node (ref "J144") (pin "3") (pinfunction "3_3") (pintype "passive"))
      (node (ref "J144") (pin "4") (pinfunction "4_4") (pintype "passive"))
      (node (ref "J144") (pin "5") (pinfunction "5_5") (pintype "passive"))
    )
    (net (code "99") (name "Net-(J145-Pad1)") (class "Default")
      (node (ref "J145") (pin "1") (pinfunction "1_1") (pintype "passive"))
      (node (ref "J145") (pin "2") (pinfunction "2_2") (pintype "passive"))
      (node (ref "J145") (pin "3") (pinfunction "3_3") (pintype "passive"))
      (node (ref "J145") (pin "4") (pinfunction "4_4") (pintype "passive"))
      (node (ref "J145") (pin "5") (pinfunction "5_5") (pintype "passive"))
    )
    (net (code "100") (name "Net-(J146-Pad1)") (class "Default")
      (node (ref "J146") (pin "1") (pinfunction "1_1") (pintype "passive"))
      (node (ref "J146") (pin "2") (pinfunction "2_2") (pintype "passive"))
      (node (ref "J146") (pin "3") (pinfunction "3_3") (pintype "passive"))
      (node (ref "J146") (pin "4") (pinfunction "4_4") (pintype "passive"))
      (node (ref "J146") (pin "5") (pinfunction "5_5") (pintype "passive"))
    )
    (net (code "101") (name "Net-(J147-Pad1)") (class "Default")
      (node (ref "J147") (pin "1") (pinfunction "1_1") (pintype "passive"))
      (node (ref "J147") (pin "2") (pinfunction "2_2") (pintype "passive"))
      (node (ref "J147") (pin "3") (pinfunction "3_3") (pintype "passive"))
      (node (ref "J147") (pin "4") (pinfunction "4_4") (pintype "passive"))
      (node (ref "J147") (pin "5") (pinfunction "5_5") (pintype "passive"))
    )
    (net (code "102") (name "Net-(J148-Pad1)") (class "Default")
      (node (ref "J148") (pin "1") (pinfunction "1_1") (pintype "passive"))
      (node (ref "J148") (pin "2") (pinfunction "2_2") (pintype "passive"))
      (node (ref "J148") (pin "3") (pinfunction "3_3") (pintype "passive"))
      (node (ref "J148") (pin "4") (pinfunction "4_4") (pintype "passive"))
      (node (ref "J148") (pin "5") (pinfunction "5_5") (pintype "passive"))
    )
    (net (code "103") (name "Net-(J149-Pad1)") (class "Default")
      (node (ref "J149") (pin "1") (pinfunction "1_1") (pintype "passive"))
      (node (ref "J149") (pin "2") (pinfunction "2_2") (pintype "passive"))
      (node (ref "J149") (pin "3") (pinfunction "3_3") (pintype "passive"))
      (node (ref "J149") (pin "4") (pinfunction "4_4") (pintype "passive"))
      (node (ref "J149") (pin "5") (pinfunction "5_5") (pintype "passive"))
    )
    (net (code "104") (name "Net-(J150-Pad1)") (class "Default")
      (node (ref "J150") (pin "1") (pinfunction "1_1") (pintype "passive"))
      (node (ref "J150") (pin "2") (pinfunction "2_2") (pintype "passive"))
      (node (ref "J150") (pin "3") (pinfunction "3_3") (pintype "passive"))
      (node (ref "J150") (pin "4") (pinfunction "4_4") (pintype "passive"))
      (node (ref "J150") (pin "5") (pinfunction "5_5") (pintype "passive"))
    )
    (net (code "105") (name "Net-(J151-Pad1)") (class "Default")
      (node (ref "J151") (pin "1") (pinfunction "1_1") (pintype "passive"))
      (node (ref "J151") (pin "2") (pinfunction "2_2") (pintype "passive"))
      (node (ref "J151") (pin "3") (pinfunction "3_3") (pintype "passive"))
      (node (ref "J151") (pin "4") (pinfunction "4_4") (pintype "passive"))
      (node (ref "J151") (pin "5") (pinfunction "5_5") (pintype "passive"))
    )
    (net (code "106") (name "Net-(J152-Pad1)") (class "Default")
      (node (ref "J152") (pin "1") (pinfunction "1_1") (pintype "passive"))
      (node (ref "J152") (pin "2") (pinfunction "2_2") (pintype "passive"))
      (node (ref "J152") (pin "3") (pinfunction "3_3") (pintype "passive"))
      (node (ref "J152") (pin "4") (pinfunction "4_4") (pintype "passive"))
      (node (ref "J152") (pin "5") (pinfunction "5_5") (pintype "passive"))
    )
    (net (code "107") (name "Net-(J153-Pad1)") (class "Default")
      (node (ref "J153") (pin "1") (pinfunction "1_1") (pintype "passive"))
      (node (ref "J153") (pin "2") (pinfunction "2_2") (pintype "passive"))
      (node (ref "J153") (pin "3") (pinfunction "3_3") (pintype "passive"))
      (node (ref "J153") (pin "4") (pinfunction "4_4") (pintype "passive"))
      (node (ref "J153") (pin "5") (pinfunction "5_5") (pintype "passive"))
    )
    (net (code "108") (name "Net-(J154-Pad1)") (class "Default")
      (node (ref "J154") (pin "1") (pinfunction "1_1") (pintype "passive"))
      (node (ref "J154") (pin "2") (pinfunction "2_2") (pintype "passive"))
      (node (ref "J154") (pin "3") (pinfunction "3_3") (pintype "passive"))
      (node (ref "J154") (pin "4") (pinfunction "4_4") (pintype "passive"))
      (node (ref "J154") (pin "5") (pinfunction "5_5") (pintype "passive"))
    )
    (net (code "109") (name "Net-(J155-Pad1)") (class "Default")
      (node (ref "J155") (pin "1") (pinfunction "1_1") (pintype "passive"))
      (node (ref "J155") (pin "2") (pinfunction "2_2") (pintype "passive"))
      (node (ref "J155") (pin "3") (pinfunction "3_3") (pintype "passive"))
      (node (ref "J155") (pin "4") (pinfunction "4_4") (pintype "passive"))
      (node (ref "J155") (pin "5") (pinfunction "5_5") (pintype "passive"))
    )
    (net (code "110") (name "Net-(J156-Pad1)") (class "Default")
      (node (ref "J156") (pin "1") (pinfunction "1_1") (pintype "passive"))
      (node (ref "J156") (pin "2") (pinfunction "2_2") (pintype "passive"))
      (node (ref "J156") (pin "3") (pinfunction "3_3") (pintype "passive"))
      (node (ref "J156") (pin "4") (pinfunction "4_4") (pintype "passive"))
      (node (ref "J156") (pin "5") (pinfunction "5_5") (pintype "passive"))
    )
    (net (code "111") (name "Net-(J157-Pad1)") (class "Default")
      (node (ref "J157") (pin "1") (pinfunction "1_1") (pintype "passive"))
      (node (ref "J157") (pin "2") (pinfunction "2_2") (pintype "passive"))
      (node (ref "J157") (pin "3") (pinfunction "3_3") (pintype "passive"))
      (node (ref "J157") (pin "4") (pinfunction "4_4") (pintype "passive"))
      (node (ref "J157") (pin "5") (pinfunction "5_5") (pintype "passive"))
    )
    (net (code "112") (name "Net-(J158-Pad1)") (class "Default")
      (node (ref "J158") (pin "1") (pinfunction "1_1") (pintype "passive"))
      (node (ref "J158") (pin "2") (pinfunction "2_2") (pintype "passive"))
      (node (ref "J158") (pin "3") (pinfunction "3_3") (pintype "passive"))
      (node (ref "J158") (pin "4") (pinfunction "4_4") (pintype "passive"))
      (node (ref "J158") (pin "5") (pinfunction "5_5") (pintype "passive"))
    )
    (net (code "113") (name "Net-(J159-Pad1)") (class "Default")
      (node (ref "J159") (pin "1") (pinfunction "1_1") (pintype "passive"))
      (node (ref "J159") (pin "2") (pinfunction "2_2") (pintype "passive"))
      (node (ref "J159") (pin "3") (pinfunction "3_3") (pintype "passive"))
      (node (ref "J159") (pin "4") (pinfunction "4_4") (pintype "passive"))
      (node (ref "J159") (pin "5") (pinfunction "5_5") (pintype "passive"))
    )
    (net (code "114") (name "Net-(J160-Pad1)") (class "Default")
      (node (ref "J160") (pin "1") (pinfunction "1_1") (pintype "passive"))
      (node (ref "J160") (pin "2") (pinfunction "2_2") (pintype "passive"))
      (node (ref "J160") (pin "3") (pinfunction "3_3") (pintype "passive"))
      (node (ref "J160") (pin "4") (pinfunction "4_4") (pintype "passive"))
      (node (ref "J160") (pin "5") (pinfunction "5_5") (pintype "passive"))
    )
    (net (code "115") (name "Net-(J161-Pad1)") (class "Default")
      (node (ref "J161") (pin "1") (pinfunction "1_1") (pintype "passive"))
      (node (ref "J161") (pin "2") (pinfunction "2_2") (pintype "passive"))
      (node (ref "J161") (pin "3") (pinfunction "3_3") (pintype "passive"))
      (node (ref "J161") (pin "4") (pinfunction "4_4") (pintype "passive"))
      (node (ref "J161") (pin "5") (pinfunction "5_5") (pintype "passive"))
    )
    (net (code "116") (name "Net-(J162-Pad1)") (class "Default")
      (node (ref "J162") (pin "1") (pinfunction "1_1") (pintype "passive"))
      (node (ref "J162") (pin "2") (pinfunction "2_2") (pintype "passive"))
      (node (ref "J162") (pin "3") (pinfunction "3_3") (pintype "passive"))
      (node (ref "J162") (pin "4") (pinfunction "4_4") (pintype "passive"))
      (node (ref "J162") (pin "5") (pinfunction "5_5") (pintype "passive"))
    )
    (net (code "117") (name "Net-(J163-Pad1)") (class "Default")
      (node (ref "J163") (pin "1") (pinfunction "1_1") (pintype "passive"))
      (node (ref "J163") (pin "2") (pinfunction "2_2") (pintype "passive"))
      (node (ref "J163") (pin "3") (pinfunction "3_3") (pintype "passive"))
      (node (ref "J163") (pin "4") (pinfunction "4_4") (pintype "passive"))
      (node (ref "J163") (pin "5") (pinfunction "5_5") (pintype "passive"))
    )
    (net (code "118") (name "Net-(J164-Pad1)") (class "Default")
      (node (ref "J164") (pin "1") (pinfunction "1_1") (pintype "passive"))
      (node (ref "J164") (pin "2") (pinfunction "2_2") (pintype "passive"))
      (node (ref "J164") (pin "3") (pinfunction "3_3") (pintype "passive"))
      (node (ref "J164") (pin "4") (pinfunction "4_4") (pintype "passive"))
      (node (ref "J164") (pin "5") (pinfunction "5_5") (pintype "passive"))
    )
    (net (code "119") (name "Net-(J165-Pad1)") (class "Default")
      (node (ref "J165") (pin "1") (pinfunction "1_1") (pintype "passive"))
      (node (ref "J165") (pin "2") (pinfunction "2_2") (pintype "passive"))
      (node (ref "J165") (pin "3") (pinfunction "3_3") (pintype "passive"))
      (node (ref "J165") (pin "4") (pinfunction "4_4") (pintype "passive"))
      (node (ref "J165") (pin "5") (pinfunction "5_5") (pintype "passive"))
    )
    (net (code "120") (name "Net-(J166-Pad1)") (class "Default")
      (node (ref "J166") (pin "1") (pinfunction "1_1") (pintype "passive"))
      (node (ref "J166") (pin "2") (pinfunction "2_2") (pintype "passive"))
      (node (ref "J166") (pin "3") (pinfunction "3_3") (pintype "passive"))
      (node (ref "J166") (pin "4") (pinfunction "4_4") (pintype "passive"))
      (node (ref "J166") (pin "5") (pinfunction "5_5") (pintype "passive"))
    )
    (net (code "121") (name "Net-(J167-Pad1)") (class "Default")
      (node (ref "J167") (pin "1") (pinfunction "1_1") (pintype "passive"))
      (node (ref "J167") (pin "2") (pinfunction "2_2") (pintype "passive"))
      (node (ref "J167") (pin "3") (pinfunction "3_3") (pintype "passive"))
      (node (ref "J167") (pin "4") (pinfunction "4_4") (pintype "passive"))
      (node (ref "J167") (pin "5") (pinfunction "5_5") (pintype "passive"))
    )
    (net (code "122") (name "Net-(J168-Pad1)") (class "Default")
      (node (ref "J168") (pin "1") (pinfunction "1_1") (pintype "passive"))
      (node (ref "J168") (pin "2") (pinfunction "2_2") (pintype "passive"))
      (node (ref "J168") (pin "3") (pinfunction "3_3") (pintype "passive"))
      (node (ref "J168") (pin "4") (pinfunction "4_4") (pintype "passive"))
      (node (ref "J168") (pin "5") (pinfunction "5_5") (pintype "passive"))
    )
    (net (code "123") (name "Net-(J169-Pad1)") (class "Default")
      (node (ref "J169") (pin "1") (pinfunction "1_1") (pintype "passive"))
      (node (ref "J169") (pin "2") (pinfunction "2_2") (pintype "passive"))
      (node (ref "J169") (pin "3") (pinfunction "3_3") (pintype "passive"))
      (node (ref "J169") (pin "4") (pinfunction "4_4") (pintype "passive"))
      (node (ref "J169") (pin "5") (pinfunction "5_5") (pintype "passive"))
    )
    (net (code "124") (name "Net-(J170-Pad1)") (class "Default")
      (node (ref "J170") (pin "1") (pinfunction "1_1") (pintype "passive"))
      (node (ref "J170") (pin "2") (pinfunction "2_2") (pintype "passive"))
      (node (ref "J170") (pin "3") (pinfunction "3_3") (pintype "passive"))
      (node (ref "J170") (pin "4") (pinfunction "4_4") (pintype "passive"))
      (node (ref "J170") (pin "5") (pinfunction "5_5") (pintype "passive"))
    )
    (net (code "125") (name "Net-(J171-Pad1)") (class "Default")
      (node (ref "J171") (pin "1") (pinfunction "1_1") (pintype "passive"))
      (node (ref "J171") (pin "2") (pinfunction "2_2") (pintype "passive"))
      (node (ref "J171") (pin "3") (pinfunction "3_3") (pintype "passive"))
      (node (ref "J171") (pin "4") (pinfunction "4_4") (pintype "passive"))
      (node (ref "J171") (pin "5") (pinfunction "5_5") (pintype "passive"))
    )
    (net (code "126") (name "Net-(J172-Pad1)") (class "Default")
      (node (ref "J172") (pin "1") (pinfunction "1_1") (pintype "passive"))
      (node (ref "J172") (pin "2") (pinfunction "2_2") (pintype "passive"))
      (node (ref "J172") (pin "3") (pinfunction "3_3") (pintype "passive"))
      (node (ref "J172") (pin "4") (pinfunction "4_4") (pintype "passive"))
      (node (ref "J172") (pin "5") (pinfunction "5_5") (pintype "passive"))
    )
    (net (code "127") (name "Net-(J173-Pad1)") (class "Default")
      (node (ref "J173") (pin "1") (pinfunction "1_1") (pintype "passive"))
      (node (ref "J173") (pin "2") (pinfunction "2_2") (pintype "passive"))
      (node (ref "J173") (pin "3") (pinfunction "3_3") (pintype "passive"))
      (node (ref "J173") (pin "4") (pinfunction "4_4") (pintype "passive"))
      (node (ref "J173") (pin "5") (pinfunction "5_5") (pintype "passive"))
    )
    (net (code "128") (name "Net-(J174-Pad1)") (class "Default")
      (node (ref "J174") (pin "1") (pinfunction "1_1") (pintype "passive"))
      (node (ref "J174") (pin "2") (pinfunction "2_2") (pintype "passive"))
      (node (ref "J174") (pin "3") (pinfunction "3_3") (pintype "passive"))
      (node (ref "J174") (pin "4") (pinfunction "4_4") (pintype "passive"))
      (node (ref "J174") (pin "5") (pinfunction "5_5") (pintype "passive"))
    )
    (net (code "129") (name "Net-(J175-Pad1)") (class "Default")
      (node (ref "J175") (pin "1") (pinfunction "1_1") (pintype "passive"))
      (node (ref "J175") (pin "2") (pinfunction "2_2") (pintype "passive"))
      (node (ref "J175") (pin "3") (pinfunction "3_3") (pintype "passive"))
      (node (ref "J175") (pin "4") (pinfunction "4_4") (pintype "passive"))
      (node (ref "J175") (pin "5") (pinfunction "5_5") (pintype "passive"))
    )
    (net (code "130") (name "Net-(J176-Pad1)") (class "Default")
      (node (ref "J176") (pin "1") (pinfunction "1_1") (pintype "passive"))
      (node (ref "J176") (pin "2") (pinfunction "2_2") (pintype "passive"))
      (node (ref "J176") (pin "3") (pinfunction "3_3") (pintype "passive"))
      (node (ref "J176") (pin "4") (pinfunction "4_4") (pintype "passive"))
      (node (ref "J176") (pin "5") (pinfunction "5_5") (pintype "passive"))
    )
    (net (code "131") (name "Net-(J177-Pad1)") (class "Default")
      (node (ref "J177") (pin "1") (pinfunction "1_1") (pintype "passive"))
      (node (ref "J177") (pin "2") (pinfunction "2_2") (pintype "passive"))
      (node (ref "J177") (pin "3") (pinfunction "3_3") (pintype "passive"))
      (node (ref "J177") (pin "4") (pinfunction "4_4") (pintype "passive"))
      (node (ref "J177") (pin "5") (pinfunction "5_5") (pintype "passive"))
    )
    (net (code "132") (name "Net-(J178-Pad1)") (class "Default")
      (node (ref "J178") (pin "1") (pinfunction "1_1") (pintype "passive"))
      (node (ref "J178") (pin "2") (pinfunction "2_2") (pintype "passive"))
      (node (ref "J178") (pin "3") (pinfunction "3_3") (pintype "passive"))
      (node (ref "J178") (pin "4") (pinfunction "4_4") (pintype "passive"))
      (node (ref "J178") (pin "5") (pinfunction "5_5") (pintype "passive"))
    )
    (net (code "133") (name "Net-(J179-Pad1)") (class "Default")
      (node (ref "J179") (pin "1") (pinfunction "1_1") (pintype "passive"))
      (node (ref "J179") (pin "2") (pinfunction "2_2") (pintype "passive"))
      (node (ref "J179") (pin "3") (pinfunction "3_3") (pintype "passive"))
      (node (ref "J179") (pin "4") (pinfunction "4_4") (pintype "passive"))
      (node (ref "J179") (pin "5") (pinfunction "5_5") (pintype "passive"))
    )
    (net (code "134") (name "Net-(J180-Pad1)") (class "Default")
      (node (ref "J180") (pin "1") (pinfunction "1_1") (pintype "passive"))
      (node (ref "J180") (pin "2") (pinfunction "2_2") (pintype "passive"))
      (node (ref "J180") (pin "3") (pinfunction "3_3") (pintype "passive"))
      (node (ref "J180") (pin "4") (pinfunction "4_4") (pintype "passive"))
      (node (ref "J180") (pin "5") (pinfunction "5_5") (pintype "passive"))
    )
    (net (code "135") (name "Net-(J181-Pad1)") (class "Default")
      (node (ref "J181") (pin "1") (pinfunction "1_1") (pintype "passive"))
      (node (ref "J181") (pin "2") (pinfunction "2_2") (pintype "passive"))
      (node (ref "J181") (pin "3") (pinfunction "3_3") (pintype "passive"))
      (node (ref "J181") (pin "4") (pinfunction "4_4") (pintype "passive"))
      (node (ref "J181") (pin "5") (pinfunction "5_5") (pintype "passive"))
    )
    (net (code "136") (name "Net-(J182-Pad1)") (class "Default")
      (node (ref "J182") (pin "1") (pinfunction "1_1") (pintype "passive"))
      (node (ref "J182") (pin "2") (pinfunction "2_2") (pintype "passive"))
      (node (ref "J182") (pin "3") (pinfunction "3_3") (pintype "passive"))
      (node (ref "J182") (pin "4") (pinfunction "4_4") (pintype "passive"))
      (node (ref "J182") (pin "5") (pinfunction "5_5") (pintype "passive"))
    )
    (net (code "137") (name "Net-(J185-Pad1)") (class "Default")
      (node (ref "J185") (pin "1") (pinfunction "1_1") (pintype "passive"))
      (node (ref "J185") (pin "2") (pinfunction "2_2") (pintype "passive"))
      (node (ref "J185") (pin "3") (pinfunction "3_3") (pintype "passive"))
      (node (ref "J185") (pin "4") (pinfunction "4_4") (pintype "passive"))
    )
    (net (code "138") (name "Net-(J186-Pad1)") (class "Default")
      (node (ref "J186") (pin "1") (pinfunction "1_1") (pintype "passive"))
      (node (ref "J186") (pin "2") (pinfunction "2_2") (pintype "passive"))
      (node (ref "J186") (pin "3") (pinfunction "3_3") (pintype "passive"))
      (node (ref "J186") (pin "4") (pinfunction "4_4") (pintype "passive"))
    )
    (net (code "139") (name "Net-(J187-Pad1)") (class "Default")
      (node (ref "J187") (pin "1") (pinfunction "1_1") (pintype "passive"))
      (node (ref "J187") (pin "2") (pinfunction "2_2") (pintype "passive"))
      (node (ref "J187") (pin "3") (pinfunction "3_3") (pintype "passive"))
      (node (ref "J187") (pin "4") (pinfunction "4_4") (pintype "passive"))
    )
    (net (code "140") (name "Net-(J188-Pad1)") (class "Default")
      (node (ref "J188") (pin "1") (pinfunction "1_1") (pintype "passive"))
      (node (ref "J188") (pin "2") (pinfunction "2_2") (pintype "passive"))
      (node (ref "J188") (pin "3") (pinfunction "3_3") (pintype "passive"))
      (node (ref "J188") (pin "4") (pinfunction "4_4") (pintype "passive"))
    )
    (net (code "141") (name "Net-(J189-Pad1)") (class "Default")
      (node (ref "J189") (pin "1") (pinfunction "1_1") (pintype "passive"))
      (node (ref "J201") (pin "1") (pinfunction "1_1") (pintype "passive"))
      (node (ref "J214") (pin "1") (pinfunction "1_1") (pintype "passive"))
      (node (ref "J214") (pin "2") (pinfunction "2_2") (pintype "passive"))
      (node (ref "J214") (pin "3") (pinfunction "3_3") (pintype "passive"))
      (node (ref "J55") (pin "1") (pinfunction "1_1") (pintype "passive"))
      (node (ref "J55") (pin "2") (pinfunction "2_2") (pintype "passive"))
      (node (ref "J55") (pin "3") (pinfunction "3_3") (pintype "passive"))
      (node (ref "J55") (pin "4") (pinfunction "4_4") (pintype "passive"))
      (node (ref "J55") (pin "5") (pinfunction "5_5") (pintype "passive"))
      (node (ref "J56") (pin "1") (pinfunction "1_1") (pintype "passive"))
      (node (ref "J56") (pin "2") (pinfunction "2_2") (pintype "passive"))
      (node (ref "J56") (pin "3") (pinfunction "3_3") (pintype "passive"))
      (node (ref "J56") (pin "4") (pinfunction "4_4") (pintype "passive"))
      (node (ref "J56") (pin "5") (pinfunction "5_5") (pintype "passive"))
      (node (ref "J57") (pin "1") (pinfunction "1_1") (pintype "passive"))
      (node (ref "J57") (pin "2") (pinfunction "2_2") (pintype "passive"))
      (node (ref "J57") (pin "3") (pinfunction "3_3") (pintype "passive"))
      (node (ref "J57") (pin "4") (pinfunction "4_4") (pintype "passive"))
      (node (ref "J57") (pin "5") (pinfunction "5_5") (pintype "passive"))
      (node (ref "J58") (pin "1") (pinfunction "1_1") (pintype "passive"))
      (node (ref "J58") (pin "2") (pinfunction "2_2") (pintype "passive"))
      (node (ref "J58") (pin "3") (pinfunction "3_3") (pintype "passive"))
      (node (ref "J58") (pin "4") (pinfunction "4_4") (pintype "passive"))
      (node (ref "J58") (pin "5") (pinfunction "5_5") (pintype "passive"))
      (node (ref "J59") (pin "1") (pinfunction "1_1") (pintype "passive"))
      (node (ref "J59") (pin "2") (pinfunction "2_2") (pintype "passive"))
      (node (ref "J59") (pin "3") (pinfunction "3_3") (pintype "passive"))
      (node (ref "J59") (pin "4") (pinfunction "4_4") (pintype "passive"))
      (node (ref "J59") (pin "5") (pinfunction "5_5") (pintype "passive"))
    )
    (net (code "142") (name "Net-(J190-Pad1)") (class "Default")
      (node (ref "J190") (pin "1") (pinfunction "1_1") (pintype "passive"))
      (node (ref "J202") (pin "1") (pinfunction "1_1") (pintype "passive"))
      (node (ref "J213") (pin "1") (pinfunction "1_1") (pintype "passive"))
      (node (ref "J213") (pin "2") (pinfunction "2_2") (pintype "passive"))
      (node (ref "J213") (pin "3") (pinfunction "3_3") (pintype "passive"))
      (node (ref "J60") (pin "1") (pinfunction "1_1") (pintype "passive"))
      (node (ref "J60") (pin "2") (pinfunction "2_2") (pintype "passive"))
      (node (ref "J60") (pin "3") (pinfunction "3_3") (pintype "passive"))
      (node (ref "J60") (pin "4") (pinfunction "4_4") (pintype "passive"))
      (node (ref "J60") (pin "5") (pinfunction "5_5") (pintype "passive"))
      (node (ref "J88") (pin "1") (pinfunction "1_1") (pintype "passive"))
      (node (ref "J88") (pin "2") (pinfunction "2_2") (pintype "passive"))
      (node (ref "J88") (pin "3") (pinfunction "3_3") (pintype "passive"))
      (node (ref "J88") (pin "4") (pinfunction "4_4") (pintype "passive"))
      (node (ref "J88") (pin "5") (pinfunction "5_5") (pintype "passive"))
      (node (ref "J89") (pin "1") (pinfunction "1_1") (pintype "passive"))
      (node (ref "J89") (pin "2") (pinfunction "2_2") (pintype "passive"))
      (node (ref "J89") (pin "3") (pinfunction "3_3") (pintype "passive"))
      (node (ref "J89") (pin "4") (pinfunction "4_4") (pintype "passive"))
      (node (ref "J89") (pin "5") (pinfunction "5_5") (pintype "passive"))
      (node (ref "J90") (pin "1") (pinfunction "1_1") (pintype "passive"))
      (node (ref "J90") (pin "2") (pinfunction "2_2") (pintype "passive"))
      (node (ref "J90") (pin "3") (pinfunction "3_3") (pintype "passive"))
      (node (ref "J90") (pin "4") (pinfunction "4_4") (pintype "passive"))
      (node (ref "J90") (pin "5") (pinfunction "5_5") (pintype "passive"))
      (node (ref "J91") (pin "1") (pinfunction "1_1") (pintype "passive"))
      (node (ref "J91") (pin "2") (pinfunction "2_2") (pintype "passive"))
      (node (ref "J91") (pin "3") (pinfunction "3_3") (pintype "passive"))
      (node (ref "J91") (pin "4") (pinfunction "4_4") (pintype "passive"))
      (node (ref "J91") (pin "5") (pinfunction "5_5") (pintype "passive"))
    )
    (net (code "143") (name "Net-(J191-Pad1)") (class "Default")
      (node (ref "J191") (pin "1") (pinfunction "1_1") (pintype "passive"))
      (node (ref "J191") (pin "2") (pinfunction "2_2") (pintype "passive"))
      (node (ref "J191") (pin "3") (pinfunction "3_3") (pintype "passive"))
      (node (ref "J191") (pin "4") (pinfunction "4_4") (pintype "passive"))
    )
    (net (code "144") (name "Net-(J192-Pad1)") (class "Default")
      (node (ref "J192") (pin "1") (pinfunction "1_1") (pintype "passive"))
      (node (ref "J192") (pin "2") (pinfunction "2_2") (pintype "passive"))
      (node (ref "J192") (pin "3") (pinfunction "3_3") (pintype "passive"))
      (node (ref "J192") (pin "4") (pinfunction "4_4") (pintype "passive"))
    )
    (net (code "145") (name "Net-(J193-Pad1)") (class "Default")
      (node (ref "J193") (pin "1") (pinfunction "1_1") (pintype "passive"))
      (node (ref "J193") (pin "2") (pinfunction "2_2") (pintype "passive"))
      (node (ref "J193") (pin "3") (pinfunction "3_3") (pintype "passive"))
      (node (ref "J193") (pin "4") (pinfunction "4_4") (pintype "passive"))
    )
    (net (code "146") (name "Net-(J194-Pad1)") (class "Default")
      (node (ref "J194") (pin "1") (pinfunction "1_1") (pintype "passive"))
      (node (ref "J194") (pin "2") (pinfunction "2_2") (pintype "passive"))
      (node (ref "J194") (pin "3") (pinfunction "3_3") (pintype "passive"))
      (node (ref "J194") (pin "4") (pinfunction "4_4") (pintype "passive"))
    )
    (net (code "147") (name "Net-(J197-Pad1)") (class "Default")
      (node (ref "J197") (pin "1") (pinfunction "1_1") (pintype "passive"))
      (node (ref "J197") (pin "2") (pinfunction "2_2") (pintype "passive"))
      (node (ref "J197") (pin "3") (pinfunction "3_3") (pintype "passive"))
      (node (ref "J197") (pin "4") (pinfunction "4_4") (pintype "passive"))
    )
    (net (code "148") (name "Net-(J198-Pad1)") (class "Default")
      (node (ref "J198") (pin "1") (pinfunction "1_1") (pintype "passive"))
      (node (ref "J198") (pin "2") (pinfunction "2_2") (pintype "passive"))
      (node (ref "J198") (pin "3") (pinfunction "3_3") (pintype "passive"))
      (node (ref "J198") (pin "4") (pinfunction "4_4") (pintype "passive"))
    )
    (net (code "149") (name "Net-(J199-Pad1)") (class "Default")
      (node (ref "J199") (pin "1") (pinfunction "1_1") (pintype "passive"))
      (node (ref "J199") (pin "2") (pinfunction "2_2") (pintype "passive"))
      (node (ref "J199") (pin "3") (pinfunction "3_3") (pintype "passive"))
      (node (ref "J199") (pin "4") (pinfunction "4_4") (pintype "passive"))
    )
    (net (code "150") (name "Net-(J200-Pad1)") (class "Default")
      (node (ref "J200") (pin "1") (pinfunction "1_1") (pintype "passive"))
      (node (ref "J200") (pin "2") (pinfunction "2_2") (pintype "passive"))
      (node (ref "J200") (pin "3") (pinfunction "3_3") (pintype "passive"))
      (node (ref "J200") (pin "4") (pinfunction "4_4") (pintype "passive"))
    )
    (net (code "151") (name "Net-(J203-Pad1)") (class "Default")
      (node (ref "J203") (pin "1") (pinfunction "1_1") (pintype "passive"))
      (node (ref "J203") (pin "2") (pinfunction "2_2") (pintype "passive"))
      (node (ref "J203") (pin "3") (pinfunction "3_3") (pintype "passive"))
      (node (ref "J203") (pin "4") (pinfunction "4_4") (pintype "passive"))
    )
    (net (code "152") (name "Net-(J204-Pad1)") (class "Default")
      (node (ref "J204") (pin "1") (pinfunction "1_1") (pintype "passive"))
      (node (ref "J204") (pin "2") (pinfunction "2_2") (pintype "passive"))
      (node (ref "J204") (pin "3") (pinfunction "3_3") (pintype "passive"))
      (node (ref "J204") (pin "4") (pinfunction "4_4") (pintype "passive"))
    )
    (net (code "153") (name "Net-(J205-Pad1)") (class "Default")
      (node (ref "J205") (pin "1") (pinfunction "1_1") (pintype "passive"))
      (node (ref "J205") (pin "2") (pinfunction "2_2") (pintype "passive"))
      (node (ref "J205") (pin "3") (pinfunction "3_3") (pintype "passive"))
      (node (ref "J205") (pin "4") (pinfunction "4_4") (pintype "passive"))
    )
    (net (code "154") (name "Net-(J206-Pad1)") (class "Default")
      (node (ref "J206") (pin "1") (pinfunction "1_1") (pintype "passive"))
      (node (ref "J206") (pin "2") (pinfunction "2_2") (pintype "passive"))
      (node (ref "J206") (pin "3") (pinfunction "3_3") (pintype "passive"))
      (node (ref "J206") (pin "4") (pinfunction "4_4") (pintype "passive"))
    )
    (net (code "155") (name "Net-(J207-Pad1)") (class "Default")
      (node (ref "J207") (pin "1") (pinfunction "1_1") (pintype "passive"))
      (node (ref "J207") (pin "2") (pinfunction "2_2") (pintype "passive"))
      (node (ref "J207") (pin "3") (pinfunction "3_3") (pintype "passive"))
      (node (ref "J207") (pin "4") (pinfunction "4_4") (pintype "passive"))
      (node (ref "J207") (pin "5") (pinfunction "5_5") (pintype "passive"))
    )
    (net (code "156") (name "Net-(J208-Pad1)") (class "Default")
      (node (ref "J208") (pin "1") (pinfunction "1_1") (pintype "passive"))
      (node (ref "J208") (pin "2") (pinfunction "2_2") (pintype "passive"))
      (node (ref "J208") (pin "3") (pinfunction "3_3") (pintype "passive"))
      (node (ref "J208") (pin "4") (pinfunction "4_4") (pintype "passive"))
      (node (ref "J208") (pin "5") (pinfunction "5_5") (pintype "passive"))
    )
    (net (code "157") (name "Net-(J209-Pad1)") (class "Default")
      (node (ref "J209") (pin "1") (pinfunction "1_1") (pintype "passive"))
      (node (ref "J209") (pin "2") (pinfunction "2_2") (pintype "passive"))
      (node (ref "J209") (pin "3") (pinfunction "3_3") (pintype "passive"))
      (node (ref "J209") (pin "4") (pinfunction "4_4") (pintype "passive"))
      (node (ref "J209") (pin "5") (pinfunction "5_5") (pintype "passive"))
    )
    (net (code "158") (name "Net-(J210-Pad1)") (class "Default")
      (node (ref "J210") (pin "1") (pinfunction "1_1") (pintype "passive"))
      (node (ref "J210") (pin "2") (pinfunction "2_2") (pintype "passive"))
      (node (ref "J210") (pin "3") (pinfunction "3_3") (pintype "passive"))
      (node (ref "J210") (pin "4") (pinfunction "4_4") (pintype "passive"))
      (node (ref "J210") (pin "5") (pinfunction "5_5") (pintype "passive"))
    )
    (net (code "159") (name "Net-(J211-Pad1)") (class "Default")
      (node (ref "J211") (pin "1") (pinfunction "1_1") (pintype "passive"))
      (node (ref "J211") (pin "2") (pinfunction "2_2") (pintype "passive"))
      (node (ref "J211") (pin "3") (pinfunction "3_3") (pintype "passive"))
      (node (ref "J211") (pin "4") (pinfunction "4_4") (pintype "passive"))
      (node (ref "J211") (pin "5") (pinfunction "5_5") (pintype "passive"))
    )
    (net (code "160") (name "Net-(J212-Pad1)") (class "Default")
      (node (ref "J212") (pin "1") (pinfunction "1_1") (pintype "passive"))
      (node (ref "J212") (pin "2") (pinfunction "2_2") (pintype "passive"))
      (node (ref "J212") (pin "3") (pinfunction "3_3") (pintype "passive"))
      (node (ref "J212") (pin "4") (pinfunction "4_4") (pintype "passive"))
      (node (ref "J212") (pin "5") (pinfunction "5_5") (pintype "passive"))
    )
  )
)
